# mcat-4cu-b-V2J.net
KiCad netlist of a schematic drawn in EAGLE
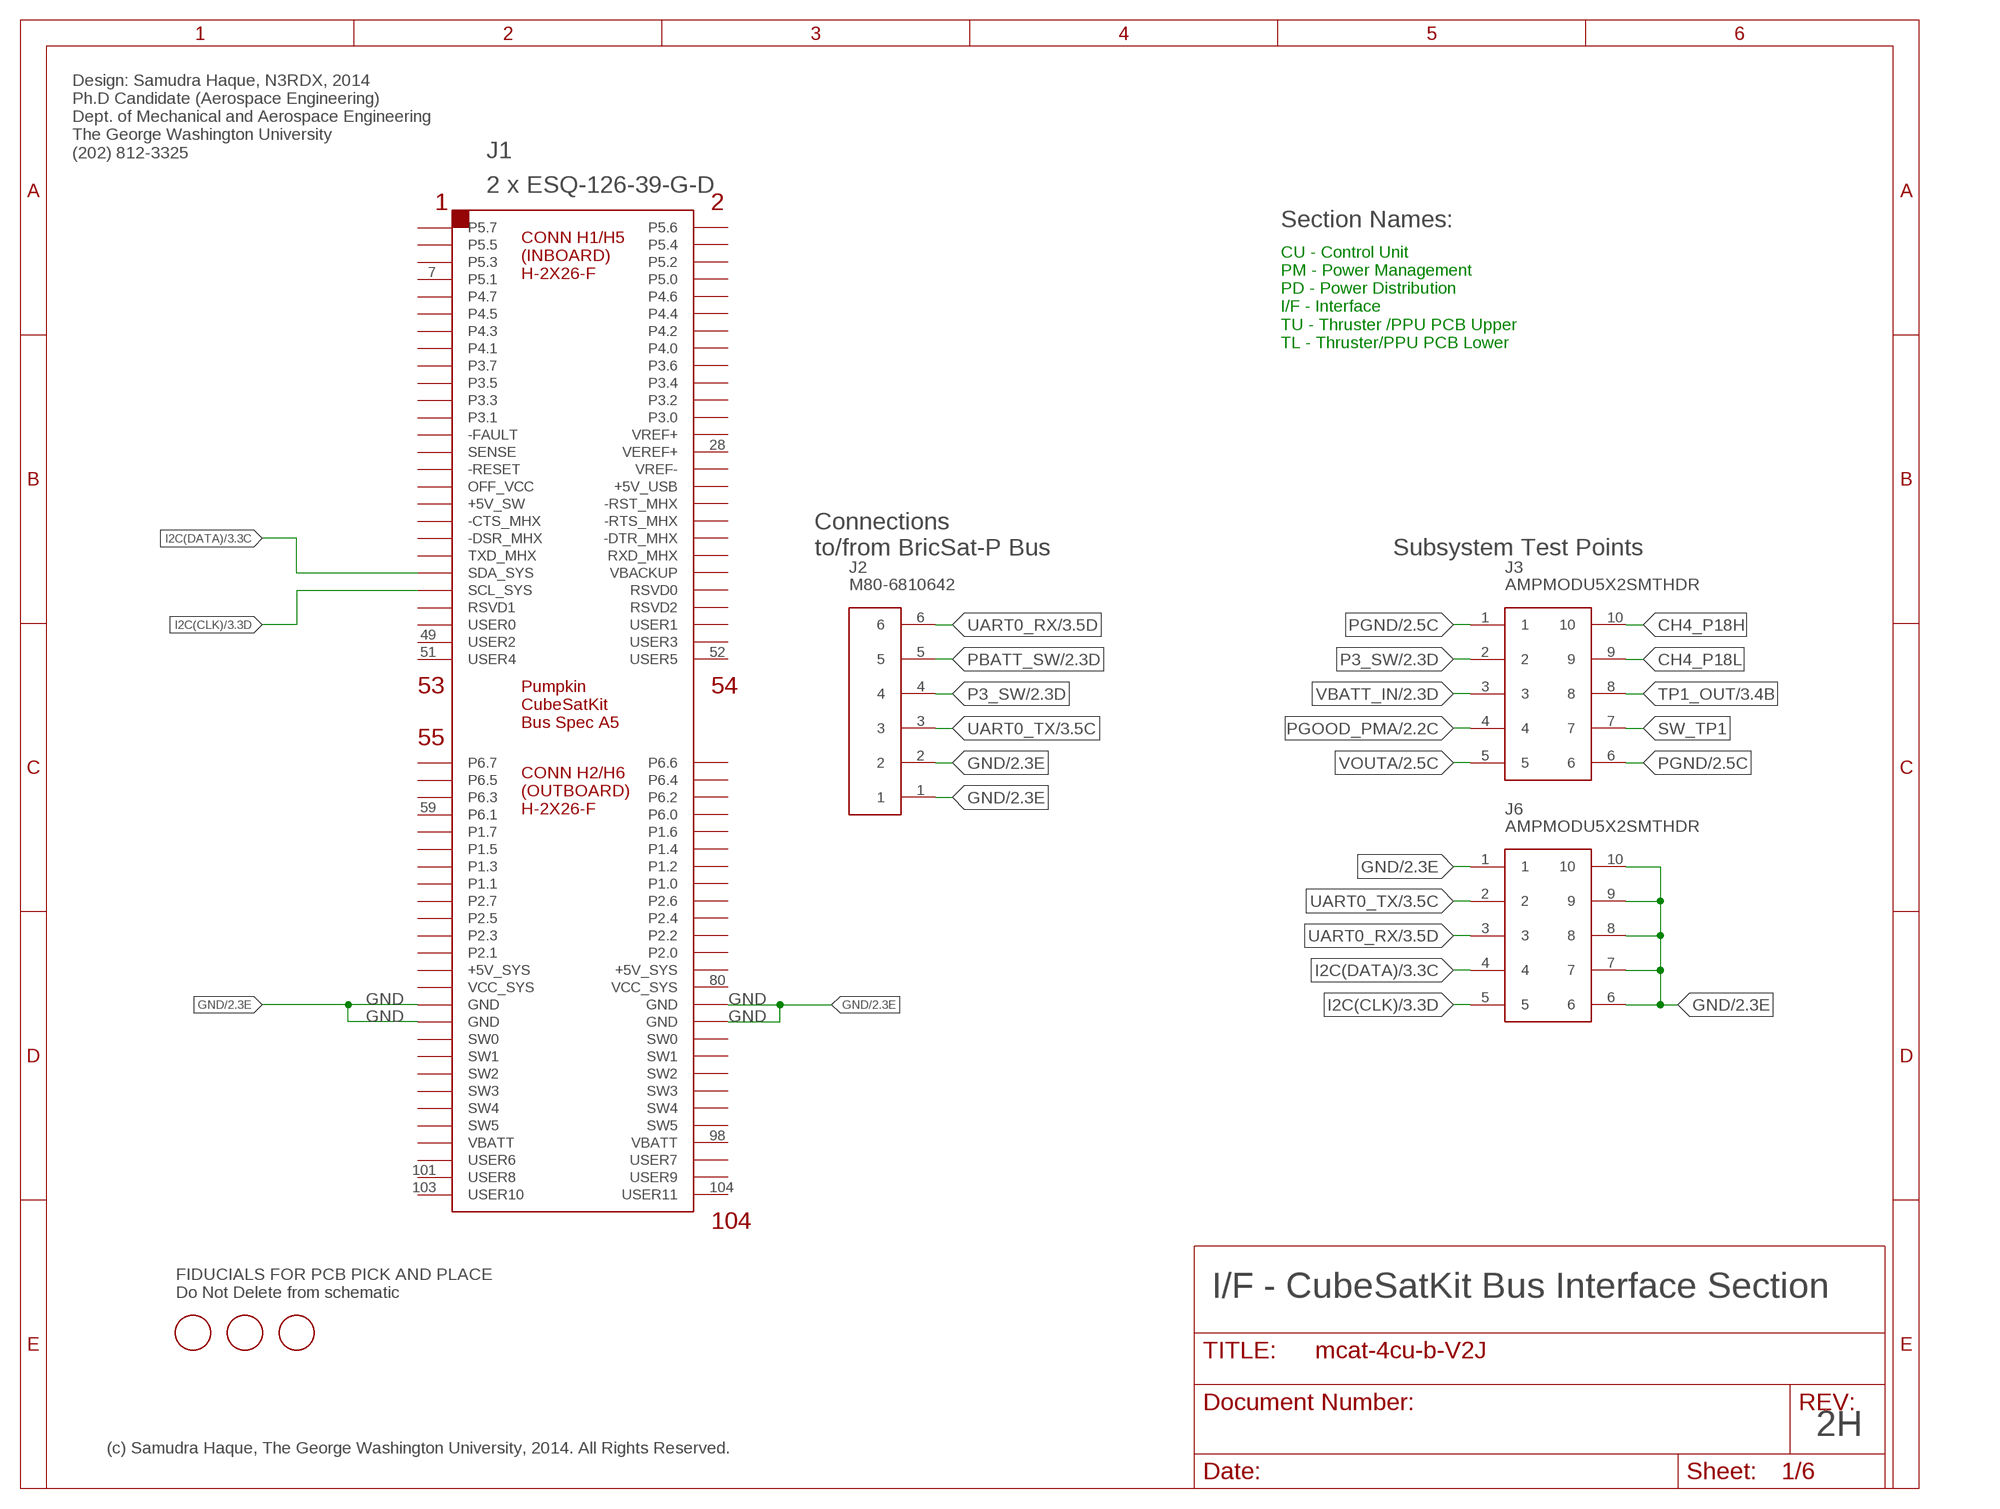
[diagram p0: schematic, sheet 1]
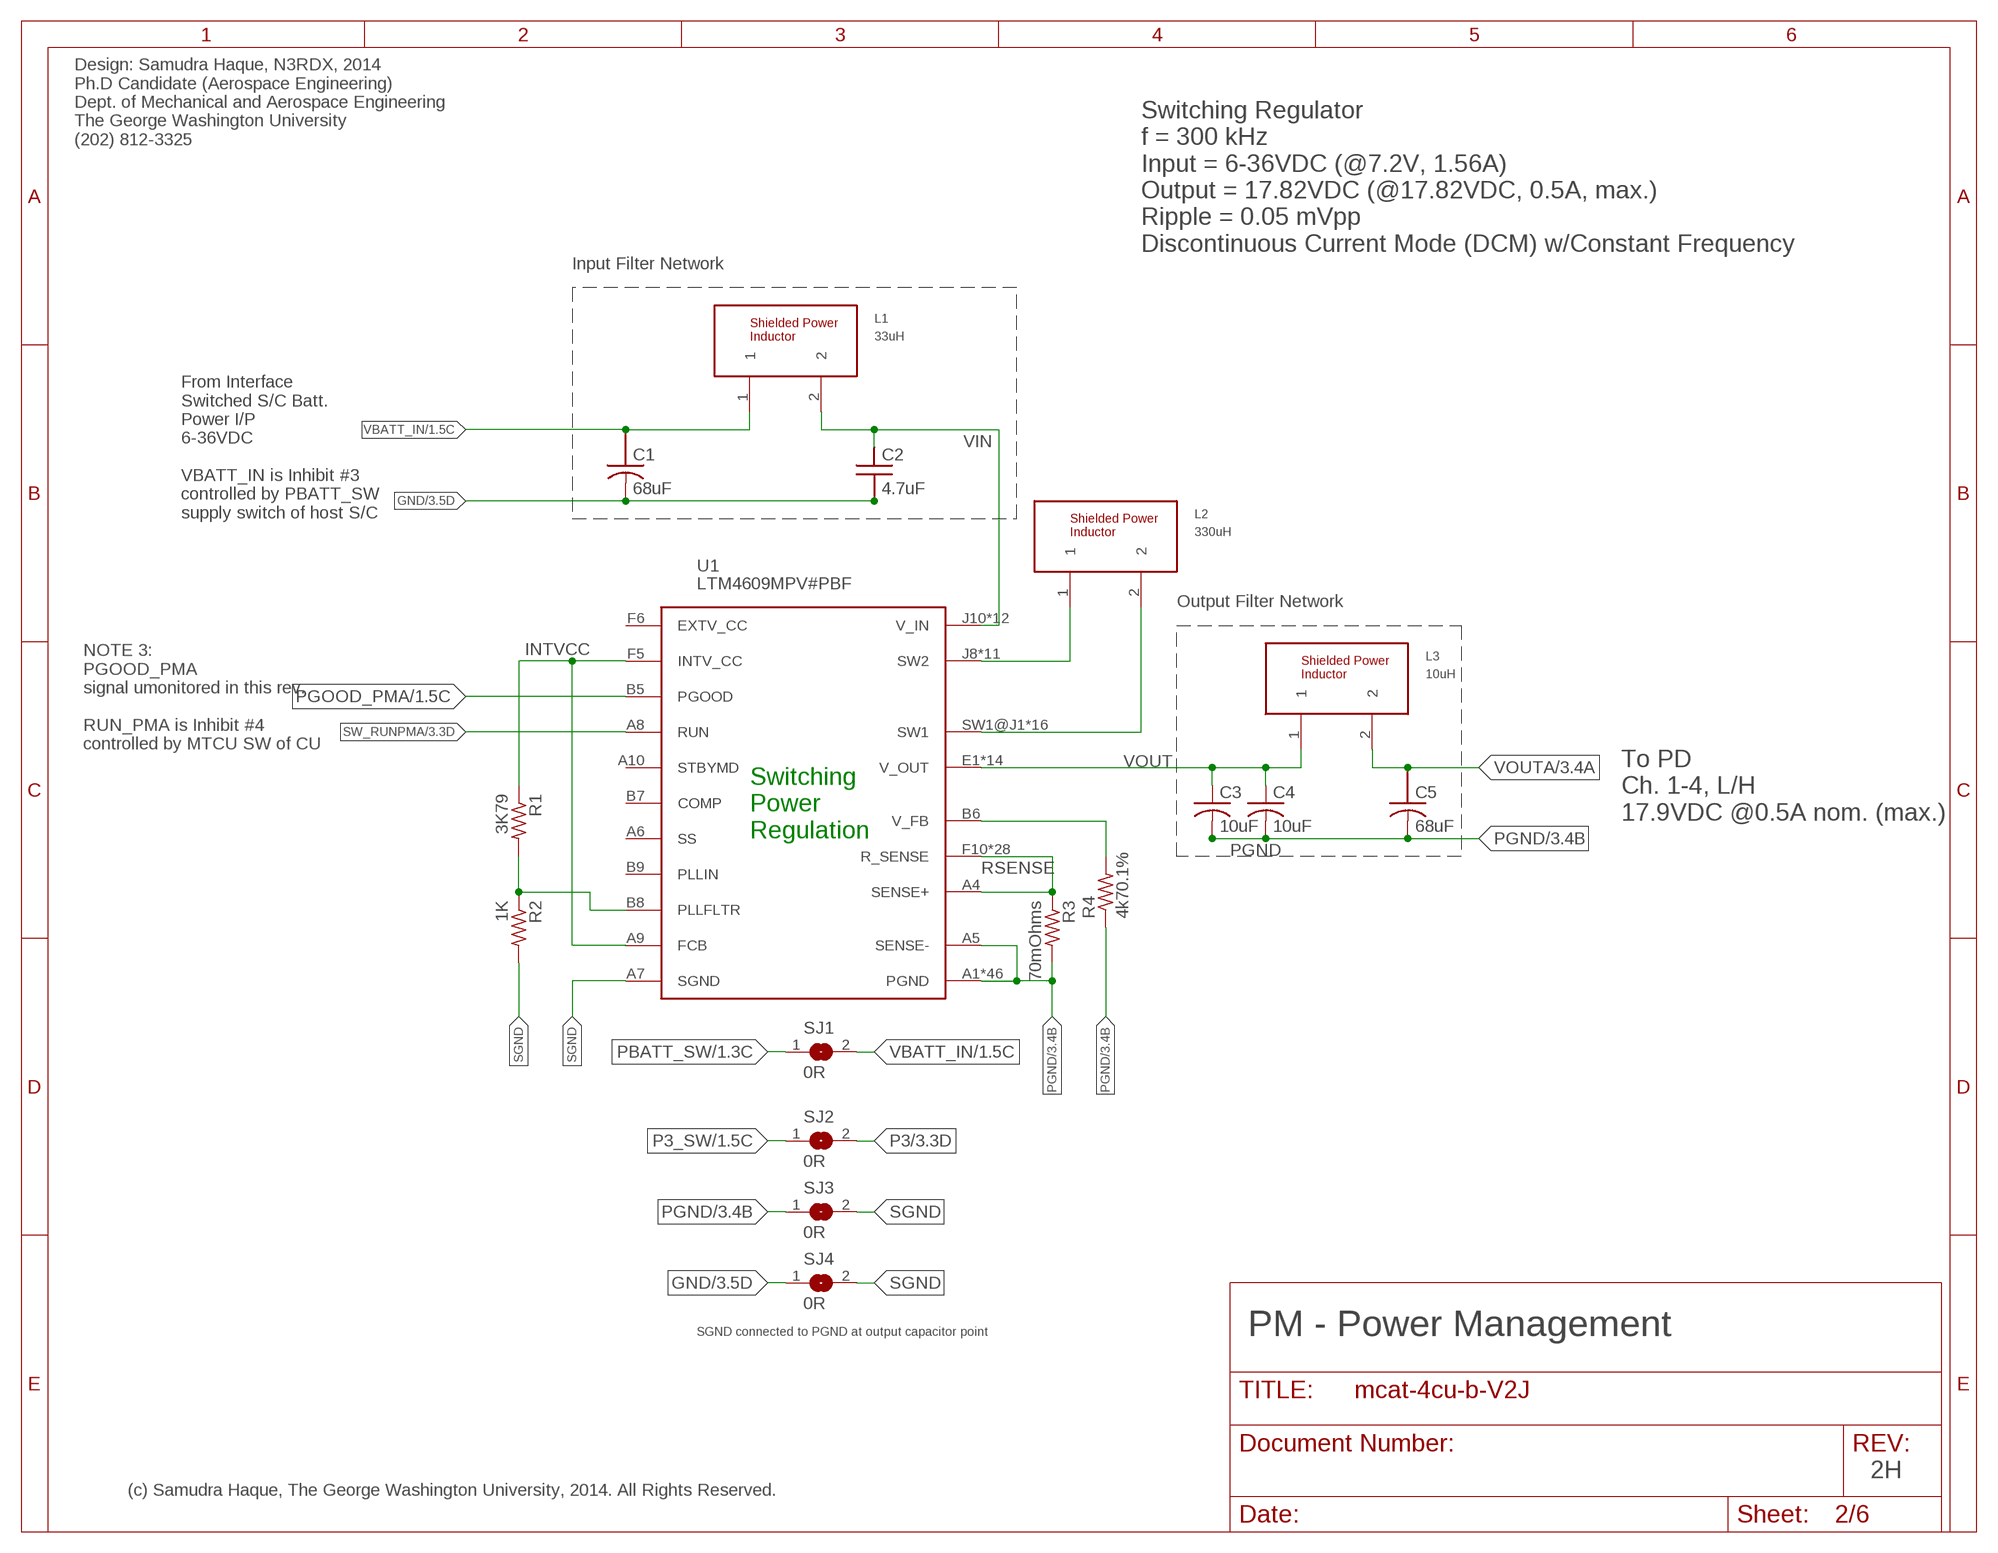
[diagram p1: schematic, sheet 2]
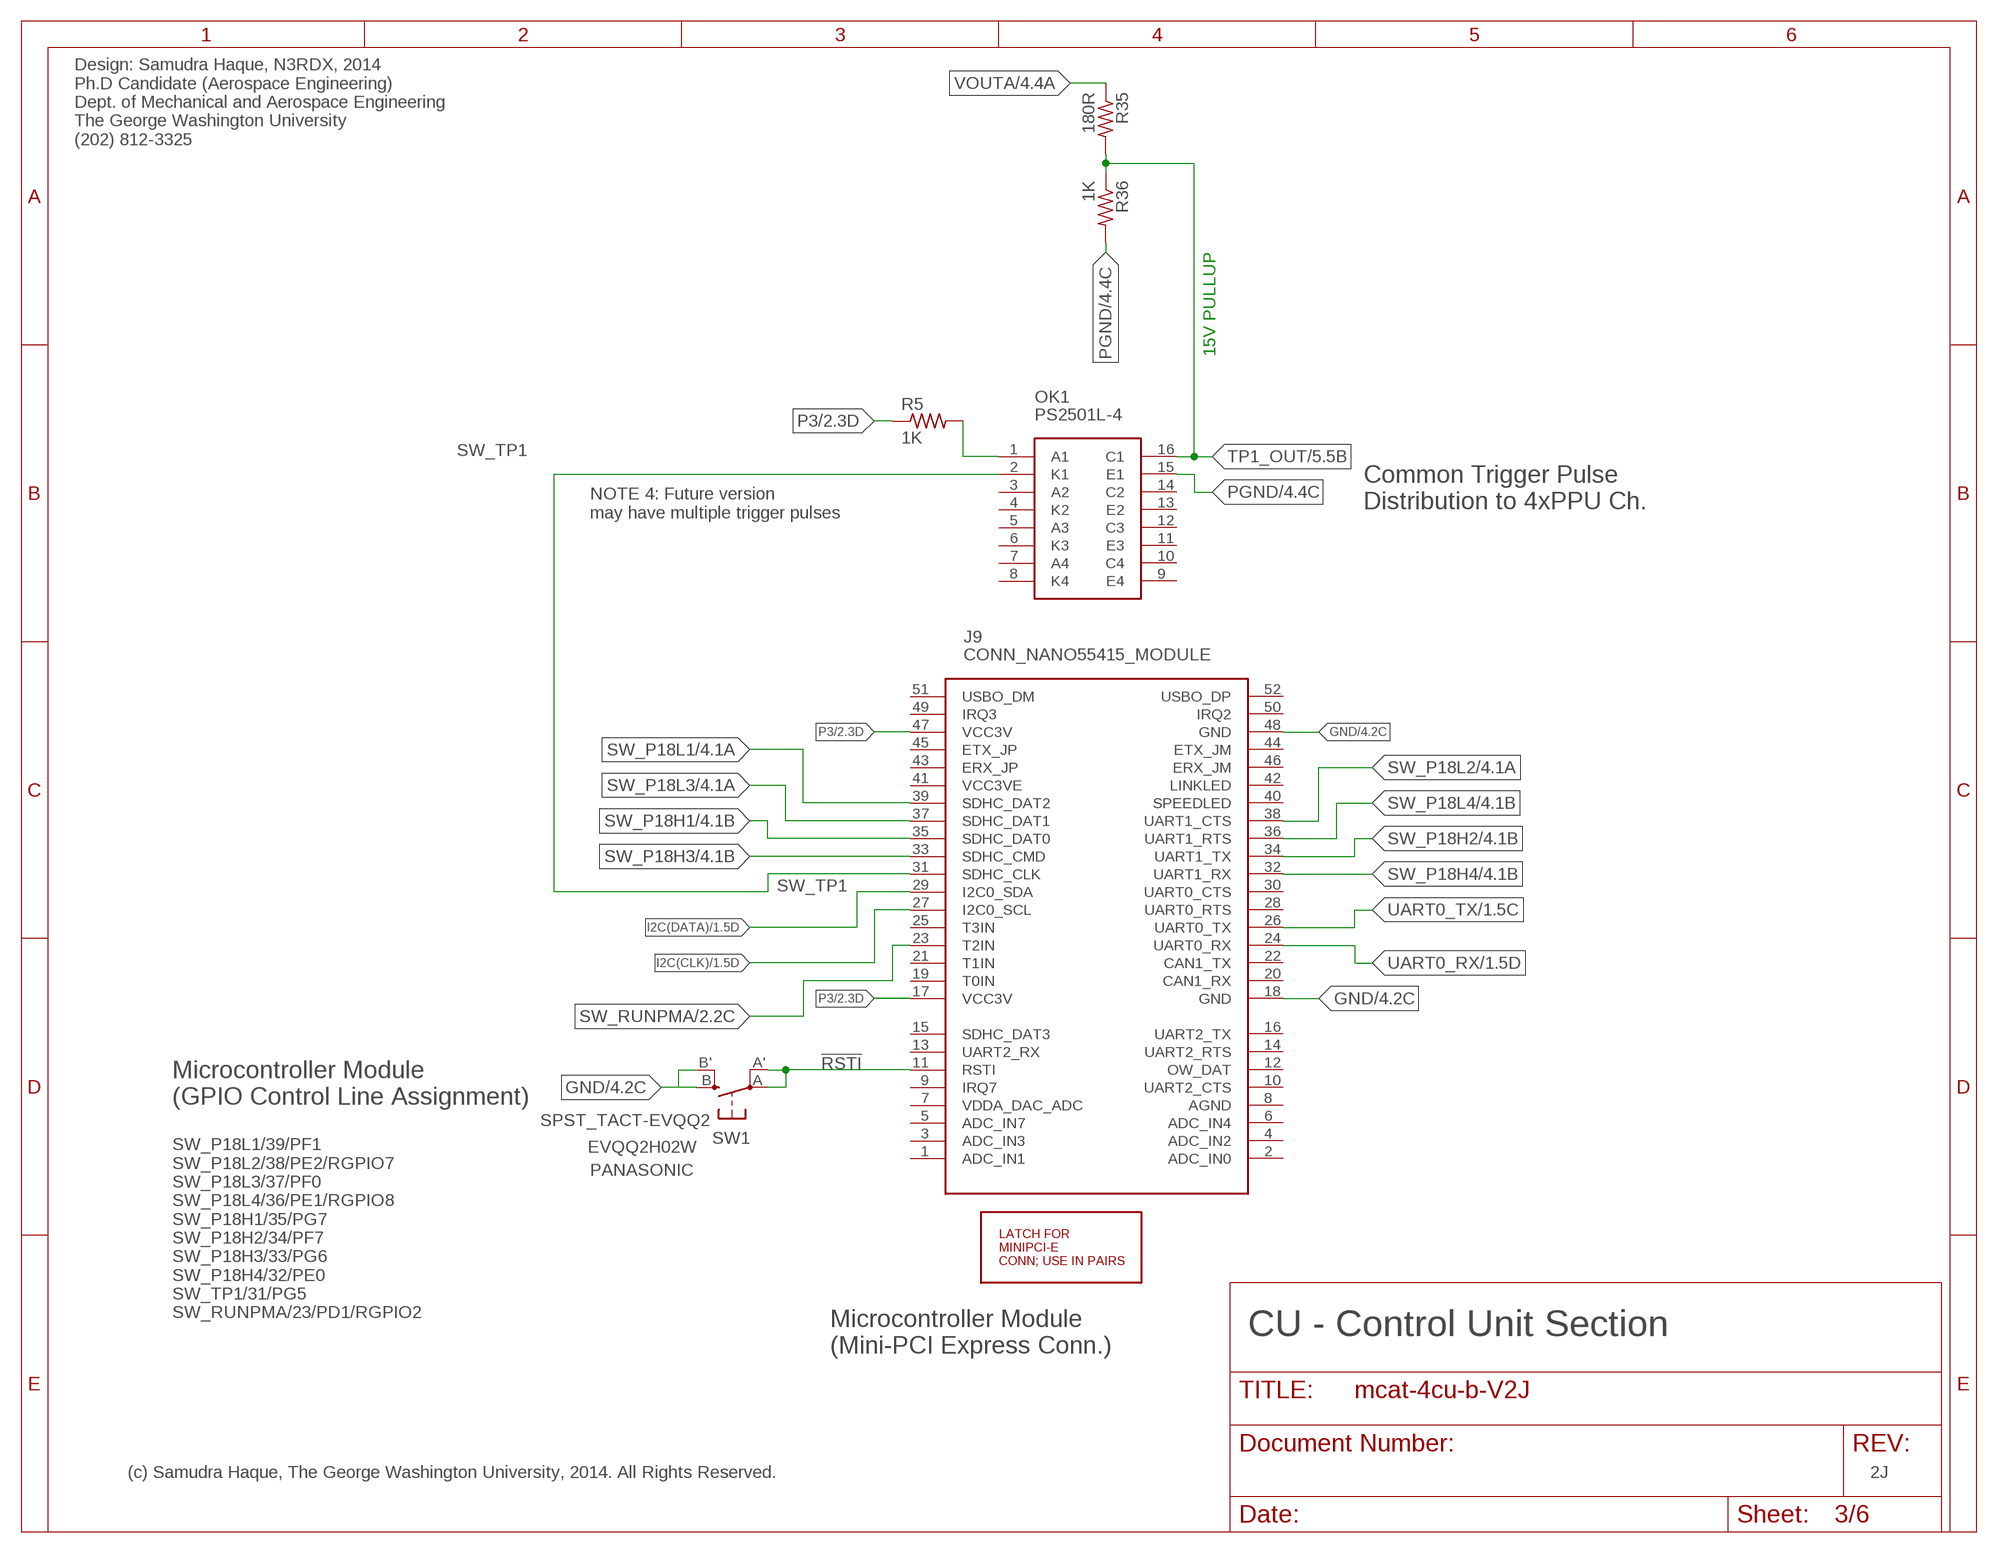
[diagram p2: schematic, sheet 3]
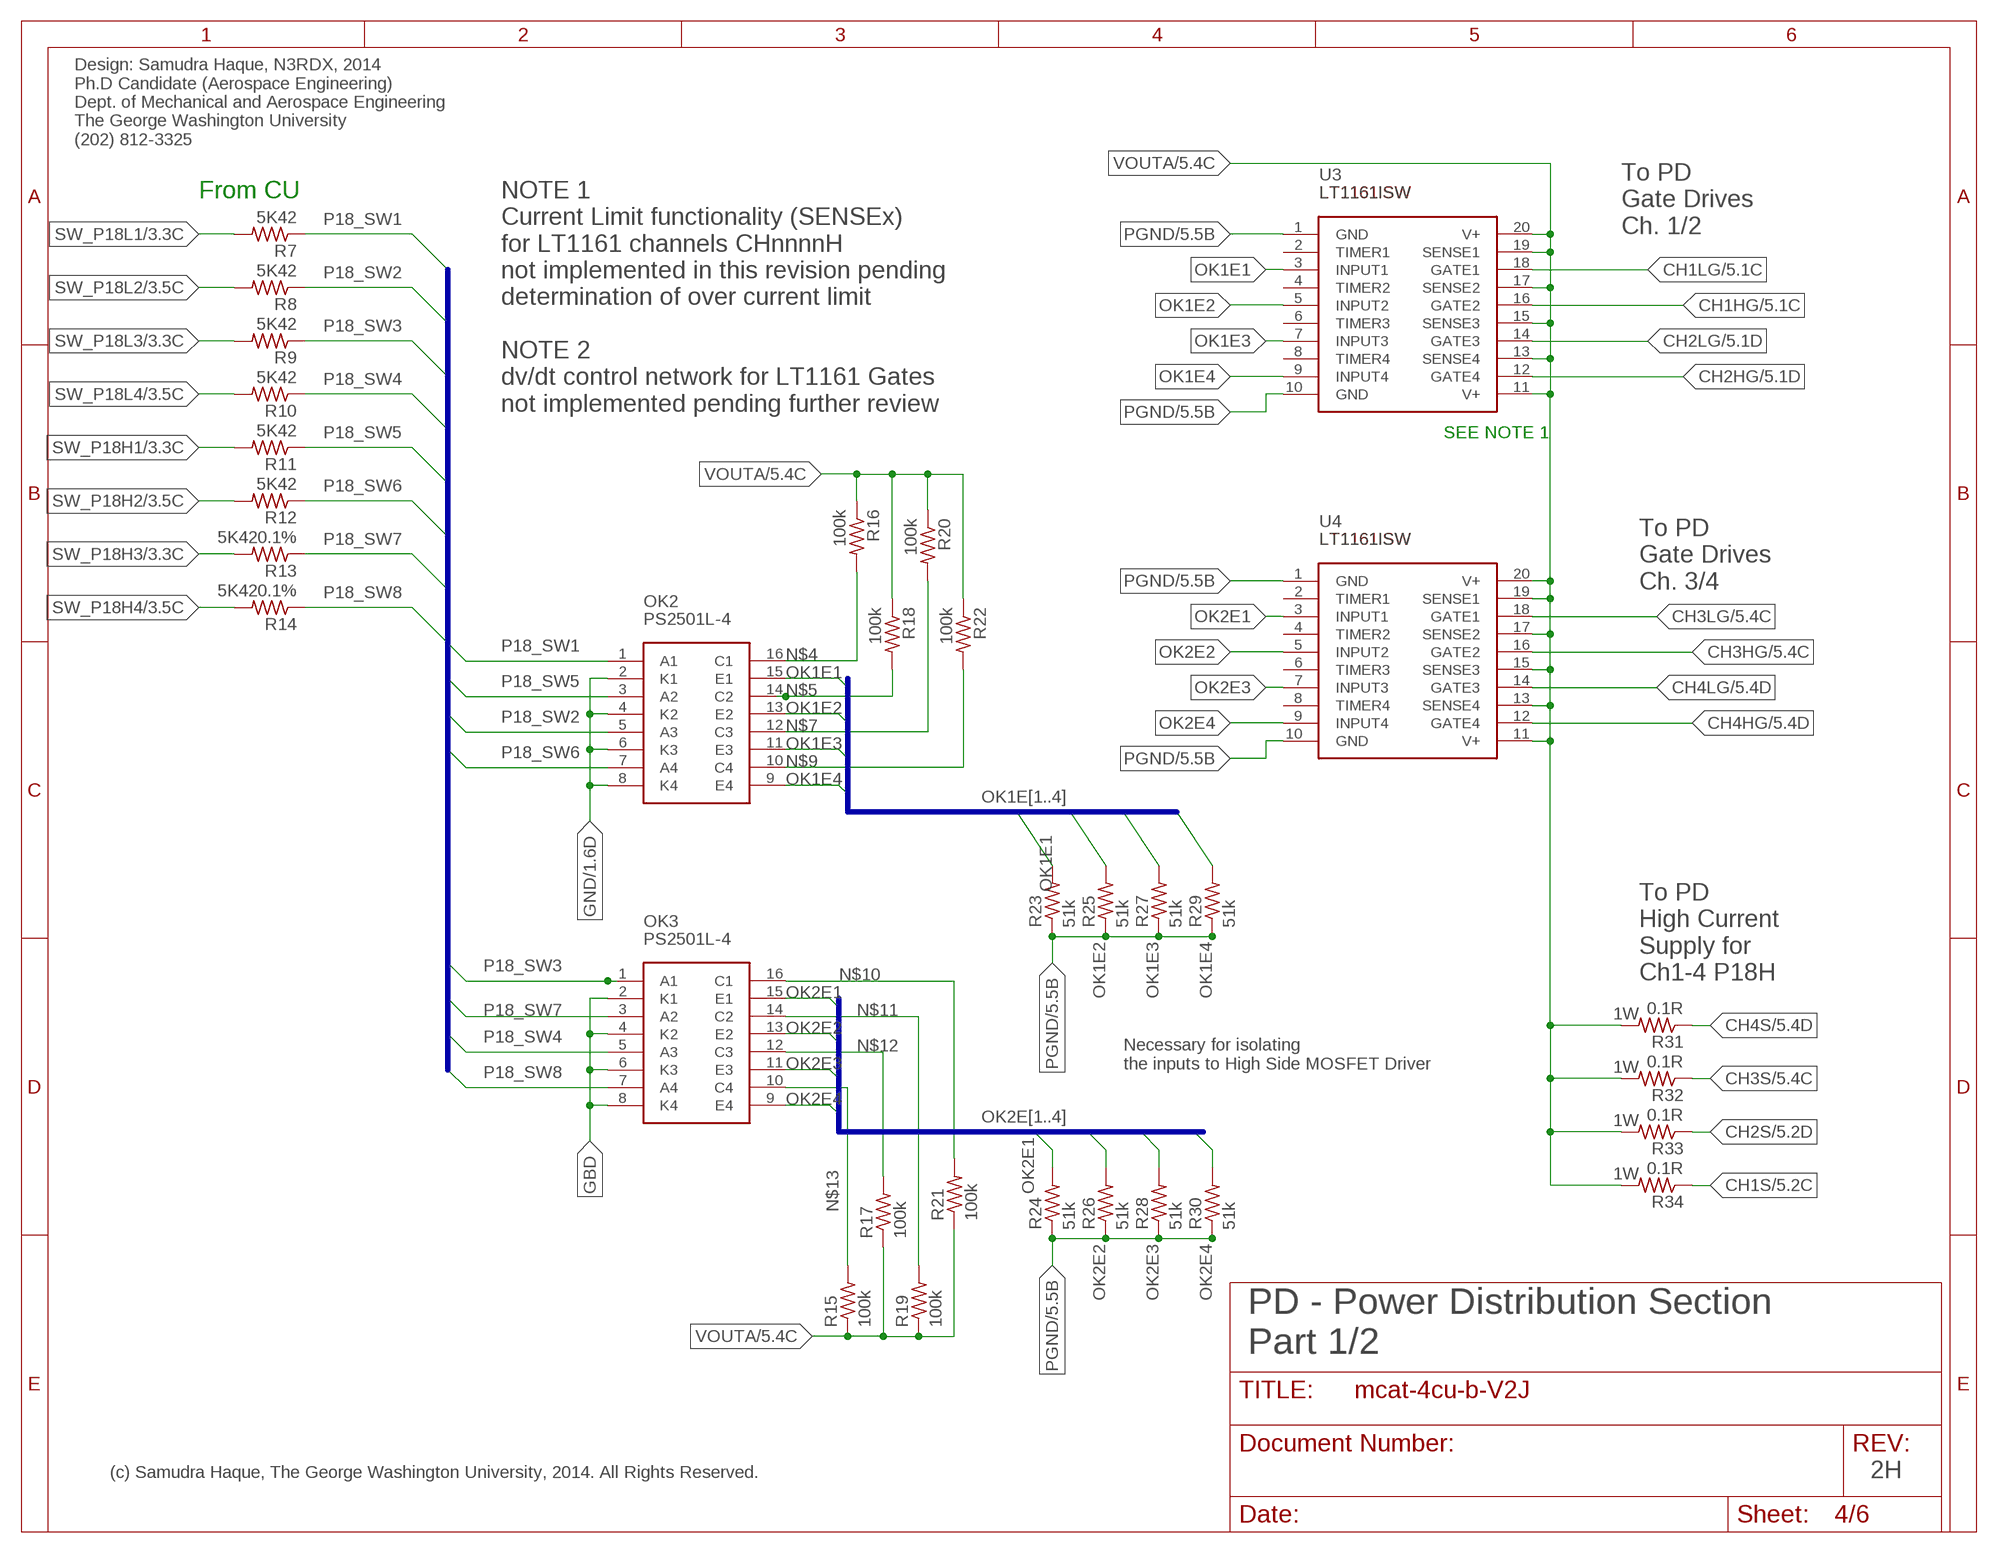
[diagram p3: schematic, sheet 4]
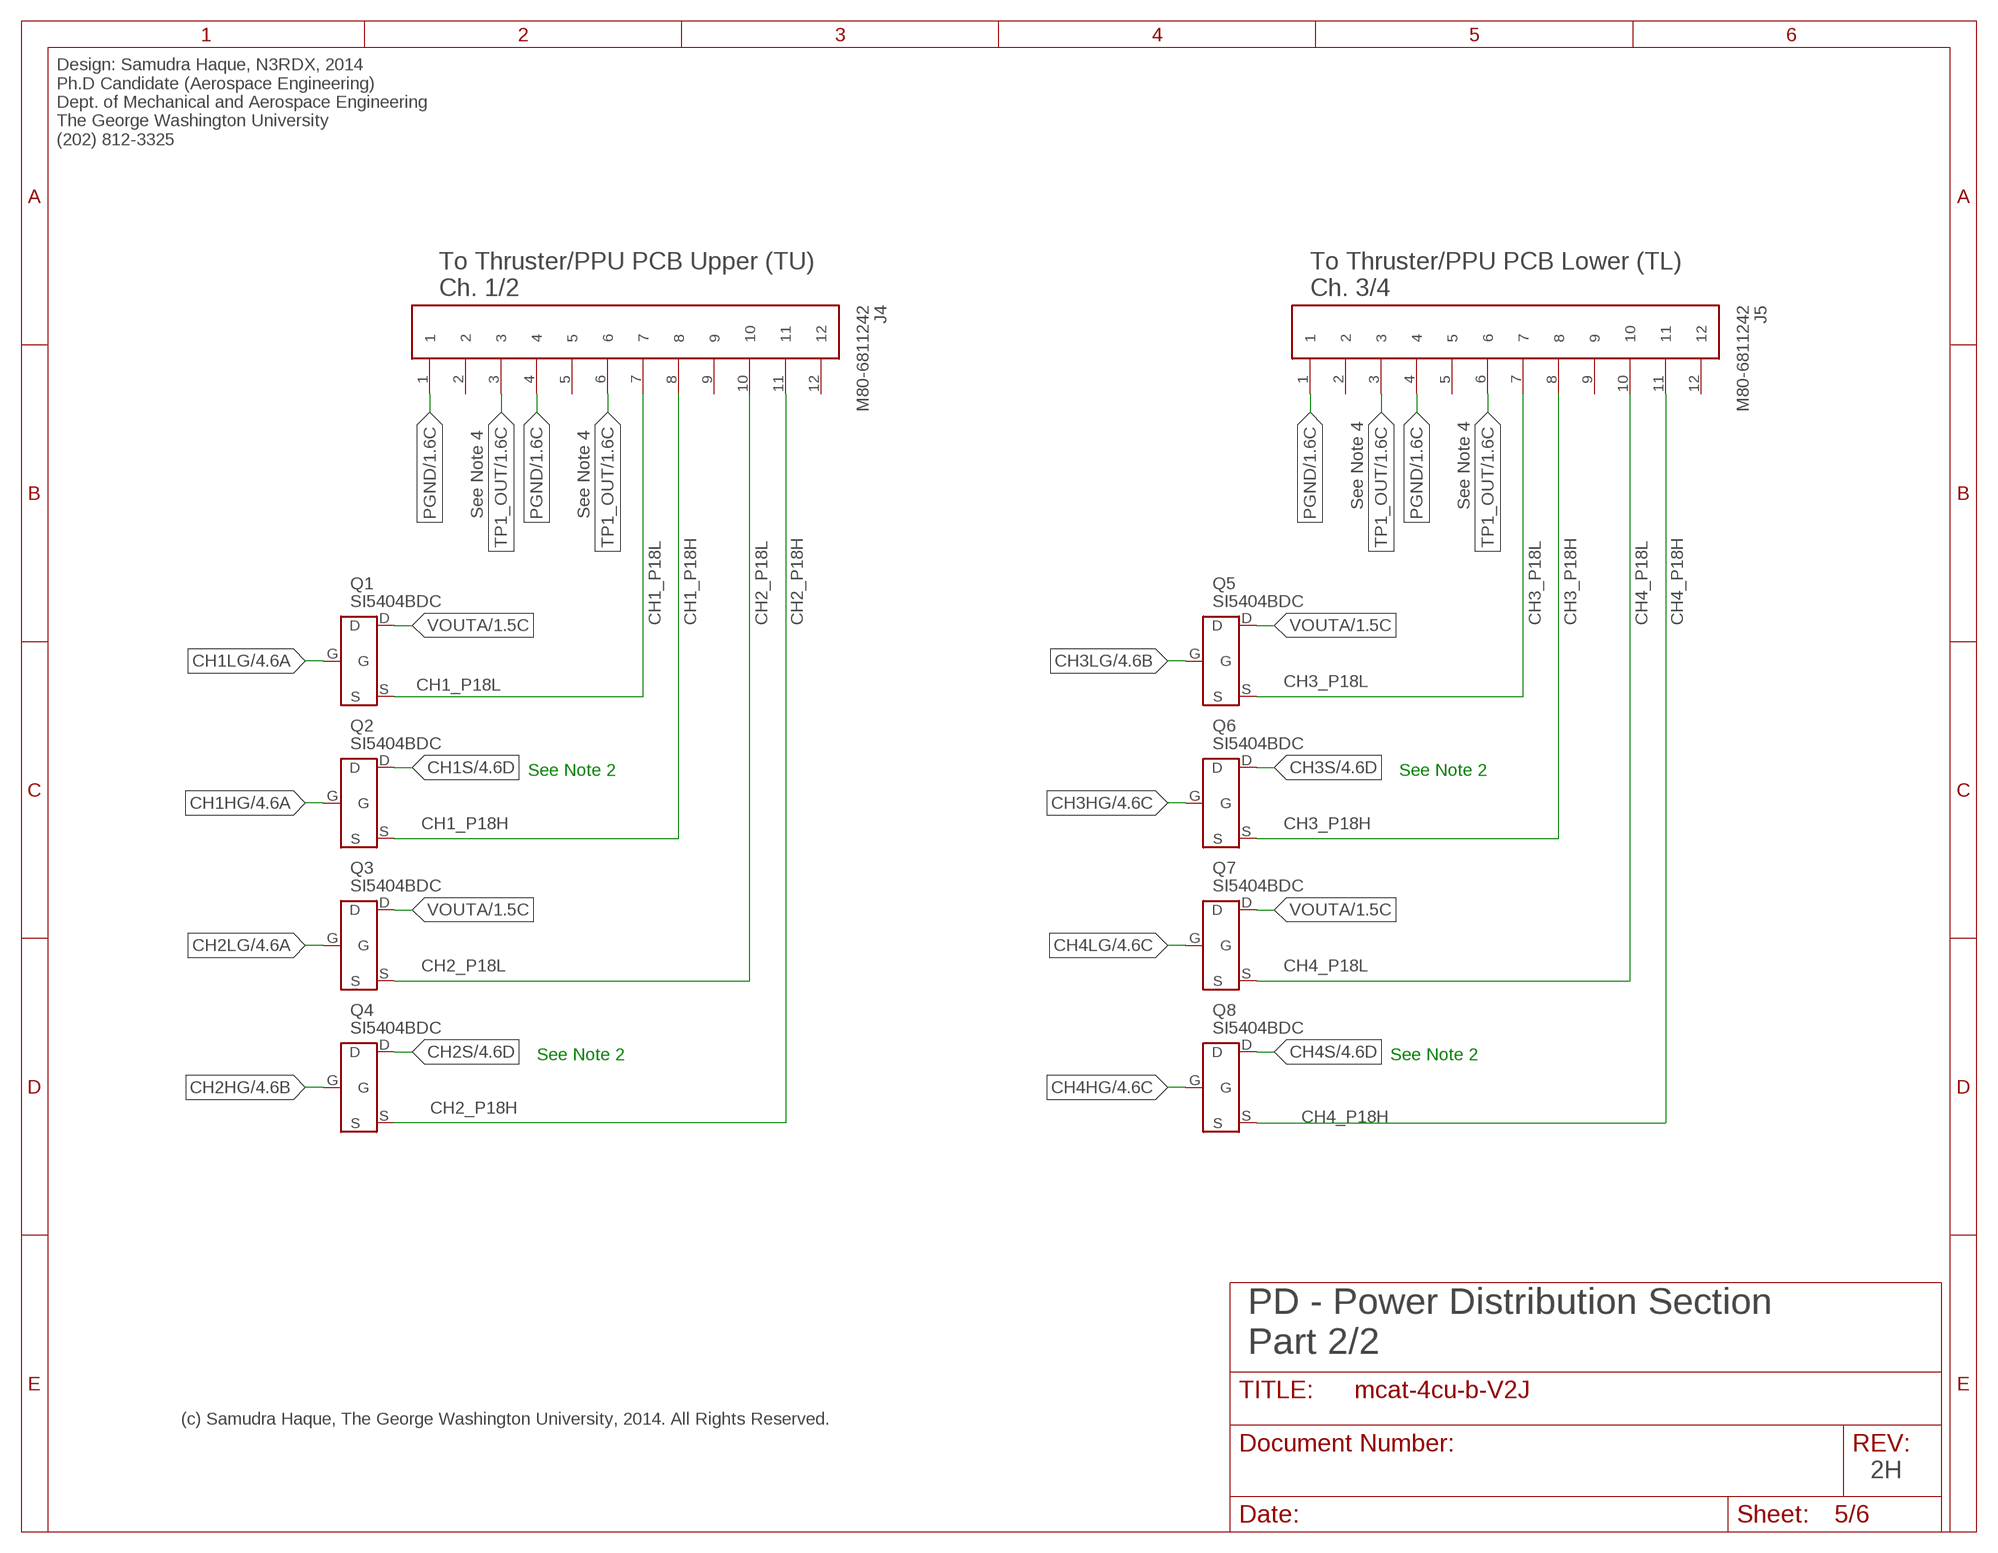
[diagram p4: schematic, sheet 5]

(export (version "E")
  (design (tool "Eeschema 10.0.6"))
  (components
    (comp (ref "J7")
      (value "LATCH_NANO55415_MODULE")
      (footprint "eagle-import:LATCH_SD-48099-400")
      (fields (field (name "MF") "MOLEX") (field (name "MPN") "SD-48099-400"))
      (libsource (lib "eagle-import") (part "LATCH_NANO55415_MODULE"))
    )
    (comp (ref "J9")
      (value "CONN_NANO55415_MODULE")
      (footprint "eagle-import:CONN_SD-67910-001")
      (fields (field (name "MF") "MOLEX") (field (name "MPN") "SD-679101-002"))
      (libsource (lib "eagle-import") (part "CONN_NANO55415_MODULE"))
    )
    (comp (ref "OK1")
      (value "PS2501L-4")
      (footprint "eagle-import:PS2501L-4")
      (fields (field (name "MF") "CEL"))
      (libsource (lib "eagle-import") (part "PS2501L-4"))
    )
    (comp (ref "R5")
      (value "1K")
      (footprint "eagle-import:R0805")
      (fields (field (name "MF") "PANASONIC") (field (name "MPN") "ERA-6AEB102V"))
      (libsource (lib "eagle-import") (part "resistor_R-US_R0805"))
    )
    (comp (ref "R35")
      (value "180R")
      (footprint "eagle-import:R0805")
      (fields (field (name "MF") "PANASONIC") (field (name "MPN") "ERA-6AED181V"))
      (libsource (lib "eagle-import") (part "resistor_R-US_R0805"))
    )
    (comp (ref "R36")
      (value "1K")
      (footprint "eagle-import:R0805")
      (fields (field (name "MF") "PANASONIC") (field (name "MPN") "ERA-6AEB102V"))
      (libsource (lib "eagle-import") (part "resistor_R-US_R0805"))
    )
    (comp (ref "SW1")
      (value "SPST_TACT-EVQQ2")
      (footprint "eagle-import:EVQ-Q2")
      (fields (field (name "MF") "PANASONIC") (field (name "MPN") "EVQQ2H02W"))
      (libsource (lib "eagle-import") (part "SPST_TACT-EVQQ2"))
    )
    (comp (ref "J4")
      (value "M80-6811242")
      (footprint "eagle-import:M80-68112")
      (fields (field (name "MF") "HARWIN"))
      (libsource (lib "eagle-import") (part "M80-6811242"))
    )
    (comp (ref "J5")
      (value "M80-6811242")
      (footprint "eagle-import:M80-68112")
      (fields (field (name "MF") "HARWIN"))
      (libsource (lib "eagle-import") (part "M80-6811242"))
    )
    (comp (ref "Q1")
      (value "SI5404BDC")
      (footprint "eagle-import:1206-8-CHIPFET")
      (fields (field (name "MF") "VISHAY/SILICONIX") (field (name "MPN") "SI5404BDC-T1-E3"))
      (libsource (lib "eagle-import") (part "SI5404BDC"))
    )
    (comp (ref "Q2")
      (value "SI5404BDC")
      (footprint "eagle-import:1206-8-CHIPFET")
      (fields (field (name "MF") "VISHAY/SILICONIX") (field (name "MPN") "SI5404BDC-T1-E3"))
      (libsource (lib "eagle-import") (part "SI5404BDC"))
    )
    (comp (ref "Q3")
      (value "SI5404BDC")
      (footprint "eagle-import:1206-8-CHIPFET")
      (fields (field (name "MF") "VISHAY/SILICONIX") (field (name "MPN") "SI5404BDC-T1-E3"))
      (libsource (lib "eagle-import") (part "SI5404BDC"))
    )
    (comp (ref "Q4")
      (value "SI5404BDC")
      (footprint "eagle-import:1206-8-CHIPFET")
      (fields (field (name "MF") "VISHAY/SILICONIX") (field (name "MPN") "SI5404BDC-T1-E3"))
      (libsource (lib "eagle-import") (part "SI5404BDC"))
    )
    (comp (ref "Q5")
      (value "SI5404BDC")
      (footprint "eagle-import:1206-8-CHIPFET")
      (fields (field (name "MF") "VISHAY/SILICONIX") (field (name "MPN") "SI5404BDC-T1-E3"))
      (libsource (lib "eagle-import") (part "SI5404BDC"))
    )
    (comp (ref "Q6")
      (value "SI5404BDC")
      (footprint "eagle-import:1206-8-CHIPFET")
      (fields (field (name "MF") "VISHAY/SILICONIX") (field (name "MPN") "SI5404BDC-T1-E3"))
      (libsource (lib "eagle-import") (part "SI5404BDC"))
    )
    (comp (ref "Q7")
      (value "SI5404BDC")
      (footprint "eagle-import:1206-8-CHIPFET")
      (fields (field (name "MF") "VISHAY/SILICONIX") (field (name "MPN") "SI5404BDC-T1-E3"))
      (libsource (lib "eagle-import") (part "SI5404BDC"))
    )
    (comp (ref "Q8")
      (value "SI5404BDC")
      (footprint "eagle-import:1206-8-CHIPFET")
      (fields (field (name "MF") "VISHAY/SILICONIX") (field (name "MPN") "SI5404BDC-T1-E3"))
      (libsource (lib "eagle-import") (part "SI5404BDC"))
    )
    (comp (ref "C1")
      (value "68uF")
      (footprint "eagle-import:OS-CON-SVPF-F12")
      (fields (field (name "MF") "OSCON") (field (name "MPN") "50SVPF68M"))
      (libsource (lib "eagle-import") (part "OSCON-50SVPF68M"))
    )
    (comp (ref "C2")
      (value "4.7uF")
      (footprint "eagle-import:MLCC-X7R-1210")
      (fields (field (name "MF") "AVX") (field (name "MPN") "LD105C475KAB2A"))
      (libsource (lib "eagle-import") (part "AVX-LD105C475KAB2A"))
    )
    (comp (ref "C3")
      (value "10uF")
      (footprint "eagle-import:C1210K")
      (fields (field (name "MF") "MURATA") (field (name "MPN") "GRM32ER71H106KA12L"))
      (libsource (lib "eagle-import") (part "C-USC1210K"))
    )
    (comp (ref "C4")
      (value "10uF")
      (footprint "eagle-import:C1210K")
      (fields (field (name "MF") "MURATA") (field (name "MPN") "GRM32ER71H106KA12L"))
      (libsource (lib "eagle-import") (part "C-USC1210K"))
    )
    (comp (ref "C5")
      (value "68uF")
      (footprint "eagle-import:OS-CON-SVPF-F12")
      (fields (field (name "MF") "OSCON") (field (name "MPN") "50SVPF68M"))
      (libsource (lib "eagle-import") (part "OSCON-50SVPF68M"))
    )
    (comp (ref "L1")
      (value "33uH")
      (footprint "eagle-import:MSS1048")
      (fields (field (name "MF") "COILCRAFT") (field (name "MPN") "MSS1038-333ML_"))
      (libsource (lib "eagle-import") (part "MSS1038-333ML_"))
    )
    (comp (ref "L2")
      (value "330uH")
      (footprint "eagle-import:MSS1048")
      (fields (field (name "MF") "COILCRAFT") (field (name "MPN") "MSS1048-334KL_"))
      (libsource (lib "eagle-import") (part "MSS1048-334KL_"))
    )
    (comp (ref "L3")
      (value "10uH")
      (footprint "eagle-import:SERIES-POWER-INDUCTORS")
      (fields (field (name "MF") "PANASONIC") (field (name "MPN") "ELL5PS100M"))
      (libsource (lib "eagle-import") (part "ELL-5PS100M"))
    )
    (comp (ref "R1")
      (value "3K79")
      (footprint "eagle-import:R0805")
      (fields (field (name "MF") "VISHAY") (field (name "MPN") "PAT0805E3791BST1"))
      (libsource (lib "eagle-import") (part "R-US_R0805"))
    )
    (comp (ref "R2")
      (value "1K")
      (footprint "eagle-import:R0805")
      (fields (field (name "MF") "VISHAY") (field (name "MPN") "PAT0805E1001BST1"))
      (libsource (lib "eagle-import") (part "R-US_R0805"))
    )
    (comp (ref "R3")
      (value "70mOhms")
      (footprint "eagle-import:R1206")
      (fields (field (name "MF") "VISHAY") (field (name "MPN") "WSL1206R0700FEB18"))
      (libsource (lib "eagle-import") (part "resistor_R-US_R1206"))
    )
    (comp (ref "R4")
      (value "4k70.1%")
      (footprint "eagle-import:R0603")
      (fields (field (name "MF") "SUSUMU") (field (name "MPN") "RG1608P-472-B-T5"))
      (libsource (lib "eagle-import") (part "resistor_R-US_R0603"))
    )
    (comp (ref "SJ1") (value "0R") (footprint "eagle-import:SJ") (libsource (lib "eagle-import") (part "SJ")))
    (comp (ref "SJ2") (value "0R") (footprint "eagle-import:SJ") (libsource (lib "eagle-import") (part "SJ")))
    (comp (ref "SJ3") (value "0R") (footprint "eagle-import:SJ") (libsource (lib "eagle-import") (part "SJ")))
    (comp (ref "SJ4") (value "0R") (footprint "eagle-import:SJ") (libsource (lib "eagle-import") (part "SJ")))
    (comp (ref "U1")
      (value "LTM4609MPV#PBF")
      (footprint "eagle-import:LGA-141-LTC-05-08-1840-B")
      (fields (field (name "MF") "Linear"))
      (libsource (lib "eagle-import") (part "LTM4609MPV#PBFROHS/HITEMP"))
    )
    (comp (ref "OK2")
      (value "PS2501L-4")
      (footprint "eagle-import:PS2501L-4")
      (fields (field (name "MF") "CEL"))
      (libsource (lib "eagle-import") (part "PS2501L-4"))
    )
    (comp (ref "OK3")
      (value "PS2501L-4")
      (footprint "eagle-import:PS2501L-4")
      (fields (field (name "MF") "CEL"))
      (libsource (lib "eagle-import") (part "PS2501L-4"))
    )
    (comp (ref "R7")
      (value "5K42")
      (footprint "eagle-import:R0805")
      (fields (field (name "MF") "VISHAY") (field (name "MPN") "TNPW08055K42BEEA"))
      (libsource (lib "eagle-import") (part "resistor_R-US_R0805"))
    )
    (comp (ref "R8")
      (value "5K42")
      (footprint "eagle-import:R0805")
      (fields (field (name "MF") "VISHAY") (field (name "MPN") "TNPW08055K42BEEA"))
      (libsource (lib "eagle-import") (part "resistor_R-US_R0805"))
    )
    (comp (ref "R9")
      (value "5K42")
      (footprint "eagle-import:R0805")
      (fields (field (name "MF") "VISHAY") (field (name "MPN") "TNPW08055K42BEEA"))
      (libsource (lib "eagle-import") (part "resistor_R-US_R0805"))
    )
    (comp (ref "R10")
      (value "5K42")
      (footprint "eagle-import:R0805")
      (fields (field (name "MF") "VISHAY") (field (name "MPN") "TNPW08055K42BEEA"))
      (libsource (lib "eagle-import") (part "resistor_R-US_R0805"))
    )
    (comp (ref "R11")
      (value "5K42")
      (footprint "eagle-import:R0805")
      (fields (field (name "MF") "VISHAY") (field (name "MPN") "TNPW08055K42BEEA"))
      (libsource (lib "eagle-import") (part "resistor_R-US_R0805"))
    )
    (comp (ref "R12")
      (value "5K42")
      (footprint "eagle-import:R0805")
      (fields (field (name "MF") "VISHAY") (field (name "MPN") "TNPW08055K42BEEA"))
      (libsource (lib "eagle-import") (part "resistor_R-US_R0805"))
    )
    (comp (ref "R13")
      (value "5K420.1%")
      (footprint "eagle-import:R0805")
      (fields (field (name "MF") "VISHAY") (field (name "MPN") "TNPW08055K42BEEA"))
      (libsource (lib "eagle-import") (part "resistor_R-US_R0805"))
    )
    (comp (ref "R14")
      (value "5K420.1%")
      (footprint "eagle-import:R0805")
      (fields (field (name "MF") "VISHAY") (field (name "MPN") "TNPW08055K42BEEA"))
      (libsource (lib "eagle-import") (part "resistor_R-US_R0805"))
    )
    (comp (ref "R15")
      (value "100k")
      (footprint "eagle-import:R0402")
      (fields (field (name "MF") "YAGEO") (field (name "MPN") "RT0402BRD07100KL"))
      (libsource (lib "eagle-import") (part "resistor_R-US_R0402"))
    )
    (comp (ref "R16")
      (value "100k")
      (footprint "eagle-import:R0402")
      (fields (field (name "MF") "YAGEO") (field (name "MPN") "RT0402BRD07100KL"))
      (libsource (lib "eagle-import") (part "resistor_R-US_R0402"))
    )
    (comp (ref "R17")
      (value "100k")
      (footprint "eagle-import:R0402")
      (fields (field (name "MF") "YAGEO") (field (name "MPN") "RT0402BRD07100KL"))
      (libsource (lib "eagle-import") (part "resistor_R-US_R0402"))
    )
    (comp (ref "R18")
      (value "100k")
      (footprint "eagle-import:R0402")
      (fields (field (name "MF") "YAGEO") (field (name "MPN") "RT0402BRD07100KL"))
      (libsource (lib "eagle-import") (part "resistor_R-US_R0402"))
    )
    (comp (ref "R19")
      (value "100k")
      (footprint "eagle-import:R0402")
      (fields (field (name "MF") "YAGEO") (field (name "MPN") "RT0402BRD07100KL"))
      (libsource (lib "eagle-import") (part "resistor_R-US_R0402"))
    )
    (comp (ref "R20")
      (value "100k")
      (footprint "eagle-import:R0402")
      (fields (field (name "MF") "YAGEO") (field (name "MPN") "RT0402BRD07100KL"))
      (libsource (lib "eagle-import") (part "resistor_R-US_R0402"))
    )
    (comp (ref "R21")
      (value "100k")
      (footprint "eagle-import:R0402")
      (fields (field (name "MF") "YAGEO") (field (name "MPN") "RT0402BRD07100KL"))
      (libsource (lib "eagle-import") (part "resistor_R-US_R0402"))
    )
    (comp (ref "R22")
      (value "100k")
      (footprint "eagle-import:R0402")
      (fields (field (name "MF") "YAGEO") (field (name "MPN") "RT0402BRD07100KL"))
      (libsource (lib "eagle-import") (part "resistor_R-US_R0402"))
    )
    (comp (ref "R23")
      (value "51k")
      (footprint "eagle-import:R0603")
      (fields (field (name "MF") "SUSUMU") (field (name "MPN") "RG1608P-513-B-T5 "))
      (libsource (lib "eagle-import") (part "resistor_R-US_R0603"))
    )
    (comp (ref "R24")
      (value "51k")
      (footprint "eagle-import:R0603")
      (fields (field (name "MF") "SUSUMU") (field (name "MPN") "RG1608P-513-B-T5"))
      (libsource (lib "eagle-import") (part "resistor_R-US_R0603"))
    )
    (comp (ref "R25")
      (value "51k")
      (footprint "eagle-import:R0603")
      (fields (field (name "MF") "SUSUMU") (field (name "MPN") "RG1608P-513-B-T5 "))
      (libsource (lib "eagle-import") (part "resistor_R-US_R0603"))
    )
    (comp (ref "R26")
      (value "51k")
      (footprint "eagle-import:R0603")
      (fields (field (name "MF") "SUSUMU") (field (name "MPN") "RG1608P-513-B-T5"))
      (libsource (lib "eagle-import") (part "resistor_R-US_R0603"))
    )
    (comp (ref "R27")
      (value "51k")
      (footprint "eagle-import:R0603")
      (fields (field (name "MF") "SUSUMU") (field (name "MPN") "RG1608P-513-B-T5"))
      (libsource (lib "eagle-import") (part "resistor_R-US_R0603"))
    )
    (comp (ref "R28")
      (value "51k")
      (footprint "eagle-import:R0603")
      (fields (field (name "MF") "SUSUMU") (field (name "MPN") "RG1608P-513-B-T5"))
      (libsource (lib "eagle-import") (part "resistor_R-US_R0603"))
    )
    (comp (ref "R29")
      (value "51k")
      (footprint "eagle-import:R0603")
      (fields (field (name "MF") "SUSUMU") (field (name "MPN") "RG1608P-513-B-T5"))
      (libsource (lib "eagle-import") (part "resistor_R-US_R0603"))
    )
    (comp (ref "R30")
      (value "51k")
      (footprint "eagle-import:R0603")
      (fields (field (name "MF") "SUSUMU") (field (name "MPN") "RG1608P-513-B-T5"))
      (libsource (lib "eagle-import") (part "resistor_R-US_R0603"))
    )
    (comp (ref "R31")
      (value "0.1R")
      (footprint "eagle-import:R1206")
      (fields
        (field (name "MF") "SUSUMU")
        (field (name "MPN") "PRL1632-R100-F-T1")
        (field (name "RATING") "1W")
      )
      (libsource (lib "eagle-import") (part "R-US_R1206"))
    )
    (comp (ref "R32")
      (value "0.1R")
      (footprint "eagle-import:R1206")
      (fields
        (field (name "MF") "SUSUMU")
        (field (name "MPN") "PRL1632-R100-F-T1")
        (field (name "RATING") "1W")
      )
      (libsource (lib "eagle-import") (part "R-US_R1206"))
    )
    (comp (ref "R33")
      (value "0.1R")
      (footprint "eagle-import:R1206")
      (fields
        (field (name "MF") "SUSUMU")
        (field (name "MPN") "PRL1632-R100-F-T1")
        (field (name "RATING") "1W")
      )
      (libsource (lib "eagle-import") (part "R-US_R1206"))
    )
    (comp (ref "R34")
      (value "0.1R")
      (footprint "eagle-import:R1206")
      (fields
        (field (name "MF") "SUSUMU")
        (field (name "MPN") "PRL1632-R100-F-T1")
        (field (name "RATING") "1W")
      )
      (libsource (lib "eagle-import") (part "R-US_R1206"))
    )
    (comp (ref "U3")
      (value "LT1161ISW")
      (footprint "eagle-import:20-LEAD-PLASTIC-SO")
      (fields (field (name "MF") "LINEAR") (field (name "MPN") "LT1161ISW#TRPBF"))
      (libsource (lib "eagle-import") (part "LT1161ISW"))
    )
    (comp (ref "U4")
      (value "LT1161ISW")
      (footprint "eagle-import:20-LEAD-PLASTIC-SO")
      (fields (field (name "MF") "LINEAR") (field (name "MPN") "LT1161ISW#TRPBF"))
      (libsource (lib "eagle-import") (part "LT1161ISW"))
    )
    (comp (ref "FID1")
      (value "FIDUCIAL")
      (footprint "eagle-import:FIDUCIAL_1MM")
      (libsource (lib "eagle-import") (part "FIDUCIAL"))
    )
    (comp (ref "FID2")
      (value "FIDUCIAL")
      (footprint "eagle-import:FIDUCIAL_1MM")
      (libsource (lib "eagle-import") (part "FIDUCIAL"))
    )
    (comp (ref "FID3")
      (value "FIDUCIAL")
      (footprint "eagle-import:FIDUCIAL_1MM")
      (libsource (lib "eagle-import") (part "FIDUCIAL"))
    )
    (comp (ref "J1")
      (value "2 x ESQ-126-39-G-D")
      (footprint "eagle-import:CSK-BUS-PKG")
      (libsource (lib "eagle-import") (part "CSK-BUS-CONN2X2X26"))
    )
    (comp (ref "J2")
      (value "M80-6810642")
      (footprint "eagle-import:M80-68106")
      (fields (field (name "MF") "HARWIN"))
      (libsource (lib "eagle-import") (part "M80-6810642"))
    )
    (comp (ref "J3")
      (value "AMPMODU5X2SMTHDR")
      (footprint "eagle-import:AMPMODU-SMT-PIN-HEADER-5X2")
      (fields (field (name "MF") "AMPMODU") (field (name "MPN") "146131-4"))
      (libsource (lib "eagle-import") (part "AMPMODU-5-146131-X(5X2)"))
    )
    (comp (ref "J6")
      (value "AMPMODU5X2SMTHDR")
      (footprint "eagle-import:AMPMODU-SMT-PIN-HEADER-5X2")
      (fields (field (name "MF") "AMPMODU") (field (name "MPN") "146131-4"))
      (libsource (lib "eagle-import") (part "AMPMODU-5-146131-X(5X2)"))
    )
  )
  (nets
    (net (code "3") (name "CH1HG") (class "Default")
      (node (ref "Q2") (pin "G") (pinfunction "G_G") (pintype "bidirectional"))
      (node (ref "U3") (pin "16") (pinfunction "GATE2_16") (pintype "bidirectional"))
    )
    (net (code "4") (name "CH1LG") (class "Default")
      (node (ref "Q1") (pin "G") (pinfunction "G_G") (pintype "bidirectional"))
      (node (ref "U3") (pin "18") (pinfunction "GATE1_18") (pintype "bidirectional"))
    )
    (net (code "5") (name "CH1S") (class "Default")
      (node (ref "Q2") (pin "D") (pinfunction "D_D") (pintype "bidirectional"))
      (node (ref "R34") (pin "1") (pinfunction "1_1") (pintype "passive"))
    )
    (net (code "6") (name "CH1_P18H") (class "Default")
      (node (ref "J4") (pin "8") (pinfunction "8_8") (pintype "bidirectional"))
      (node (ref "Q2") (pin "S") (pinfunction "S_S") (pintype "bidirectional"))
    )
    (net (code "7") (name "CH1_P18L") (class "Default")
      (node (ref "J4") (pin "7") (pinfunction "7_7") (pintype "bidirectional"))
      (node (ref "Q1") (pin "S") (pinfunction "S_S") (pintype "bidirectional"))
    )
    (net (code "8") (name "CH2HG") (class "Default")
      (node (ref "Q4") (pin "G") (pinfunction "G_G") (pintype "bidirectional"))
      (node (ref "U3") (pin "12") (pinfunction "GATE4_12") (pintype "bidirectional"))
    )
    (net (code "9") (name "CH2LG") (class "Default")
      (node (ref "Q3") (pin "G") (pinfunction "G_G") (pintype "bidirectional"))
      (node (ref "U3") (pin "14") (pinfunction "GATE3_14") (pintype "bidirectional"))
    )
    (net (code "10") (name "CH2S") (class "Default")
      (node (ref "Q4") (pin "D") (pinfunction "D_D") (pintype "bidirectional"))
      (node (ref "R33") (pin "1") (pinfunction "1_1") (pintype "passive"))
    )
    (net (code "11") (name "CH2_P18H") (class "Default")
      (node (ref "J4") (pin "11") (pinfunction "11_11") (pintype "bidirectional"))
      (node (ref "Q4") (pin "S") (pinfunction "S_S") (pintype "bidirectional"))
    )
    (net (code "12") (name "CH2_P18L") (class "Default")
      (node (ref "J4") (pin "10") (pinfunction "10_10") (pintype "bidirectional"))
      (node (ref "Q3") (pin "S") (pinfunction "S_S") (pintype "bidirectional"))
    )
    (net (code "13") (name "CH3HG") (class "Default")
      (node (ref "Q6") (pin "G") (pinfunction "G_G") (pintype "bidirectional"))
      (node (ref "U4") (pin "16") (pinfunction "GATE2_16") (pintype "bidirectional"))
    )
    (net (code "14") (name "CH3LG") (class "Default")
      (node (ref "Q5") (pin "G") (pinfunction "G_G") (pintype "bidirectional"))
      (node (ref "U4") (pin "18") (pinfunction "GATE1_18") (pintype "bidirectional"))
    )
    (net (code "15") (name "CH3S") (class "Default")
      (node (ref "Q6") (pin "D") (pinfunction "D_D") (pintype "bidirectional"))
      (node (ref "R32") (pin "1") (pinfunction "1_1") (pintype "passive"))
    )
    (net (code "16") (name "CH3_P18H") (class "Default")
      (node (ref "J5") (pin "8") (pinfunction "8_8") (pintype "bidirectional"))
      (node (ref "Q6") (pin "S") (pinfunction "S_S") (pintype "bidirectional"))
    )
    (net (code "17") (name "CH3_P18L") (class "Default")
      (node (ref "J5") (pin "7") (pinfunction "7_7") (pintype "bidirectional"))
      (node (ref "Q5") (pin "S") (pinfunction "S_S") (pintype "bidirectional"))
    )
    (net (code "18") (name "CH4HG") (class "Default")
      (node (ref "Q8") (pin "G") (pinfunction "G_G") (pintype "bidirectional"))
      (node (ref "U4") (pin "12") (pinfunction "GATE4_12") (pintype "bidirectional"))
    )
    (net (code "19") (name "CH4LG") (class "Default")
      (node (ref "Q7") (pin "G") (pinfunction "G_G") (pintype "bidirectional"))
      (node (ref "U4") (pin "14") (pinfunction "GATE3_14") (pintype "bidirectional"))
    )
    (net (code "20") (name "CH4S") (class "Default")
      (node (ref "Q8") (pin "D") (pinfunction "D_D") (pintype "bidirectional"))
      (node (ref "R31") (pin "1") (pinfunction "1_1") (pintype "passive"))
    )
    (net (code "21") (name "CH4_P18H") (class "Default")
      (node (ref "J3") (pin "10") (pinfunction "10_10") (pintype "bidirectional"))
      (node (ref "J5") (pin "11") (pinfunction "11_11") (pintype "bidirectional"))
      (node (ref "Q8") (pin "S") (pinfunction "S_S") (pintype "bidirectional"))
    )
    (net (code "22") (name "CH4_P18L") (class "Default")
      (node (ref "J3") (pin "9") (pinfunction "9_9") (pintype "bidirectional"))
      (node (ref "J5") (pin "10") (pinfunction "10_10") (pintype "bidirectional"))
      (node (ref "Q7") (pin "S") (pinfunction "S_S") (pintype "bidirectional"))
    )
    (net (code "23") (name "GBD") (class "Default")
      (node (ref "OK3") (pin "2") (pinfunction "K1_2") (pintype "bidirectional"))
      (node (ref "OK3") (pin "4") (pinfunction "K2_4") (pintype "bidirectional"))
      (node (ref "OK3") (pin "6") (pinfunction "K3_6") (pintype "bidirectional"))
      (node (ref "OK3") (pin "8") (pinfunction "K4_8") (pintype "bidirectional"))
    )
    (net (code "24") (name "GND") (class "Default")
      (node (ref "C1") (pin "K1") (pinfunction "K_K1") (pintype "passive"))
      (node (ref "C2") (pin "2") (pinfunction "2_2") (pintype "passive"))
      (node (ref "J1") (pin "81") (pinfunction "GND_81") (pintype "bidirectional"))
      (node (ref "J1") (pin "82") (pinfunction "GND_82") (pintype "bidirectional"))
      (node (ref "J1") (pin "83") (pinfunction "GND_83") (pintype "bidirectional"))
      (node (ref "J1") (pin "84") (pinfunction "GND_84") (pintype "bidirectional"))
      (node (ref "J2") (pin "1") (pinfunction "1_1") (pintype "bidirectional"))
      (node (ref "J2") (pin "2") (pinfunction "2_2") (pintype "bidirectional"))
      (node (ref "J6") (pin "1") (pinfunction "1_1") (pintype "bidirectional"))
      (node (ref "J6") (pin "10") (pinfunction "10_10") (pintype "bidirectional"))
      (node (ref "J6") (pin "6") (pinfunction "6_6") (pintype "bidirectional"))
      (node (ref "J6") (pin "7") (pinfunction "7_7") (pintype "bidirectional"))
      (node (ref "J6") (pin "8") (pinfunction "8_8") (pintype "bidirectional"))
      (node (ref "J6") (pin "9") (pinfunction "9_9") (pintype "bidirectional"))
      (node (ref "J9") (pin "18") (pinfunction "GND_18") (pintype "bidirectional"))
      (node (ref "J9") (pin "48") (pinfunction "GND_48") (pintype "bidirectional"))
      (node (ref "OK2") (pin "2") (pinfunction "K1_2") (pintype "bidirectional"))
      (node (ref "OK2") (pin "4") (pinfunction "K2_4") (pintype "bidirectional"))
      (node (ref "OK2") (pin "6") (pinfunction "K3_6") (pintype "bidirectional"))
      (node (ref "OK2") (pin "8") (pinfunction "K4_8") (pintype "bidirectional"))
      (node (ref "SJ4") (pin "1") (pinfunction "1_1") (pintype "passive"))
      (node (ref "SW1") (pin "B") (pinfunction "S_B") (pintype "passive"))
      (node (ref "SW1") (pin "B'") (pinfunction "S1_B'") (pintype "passive"))
    )
    (net (code "25") (name "I2C(CLK)") (class "Default")
      (node (ref "J1") (pin "43") (pinfunction "SCL_SYS_43") (pintype "bidirectional"))
      (node (ref "J6") (pin "5") (pinfunction "5_5") (pintype "bidirectional"))
      (node (ref "J9") (pin "27") (pinfunction "I2C0_SCL_27") (pintype "bidirectional"))
    )
    (net (code "26") (name "I2C(DATA)") (class "Default")
      (node (ref "J1") (pin "41") (pinfunction "SDA_SYS_41") (pintype "bidirectional"))
      (node (ref "J6") (pin "4") (pinfunction "4_4") (pintype "bidirectional"))
      (node (ref "J9") (pin "29") (pinfunction "I2C0_SDA_29") (pintype "bidirectional"))
    )
    (net (code "27") (name "INTVCC") (class "Default")
      (node (ref "R1") (pin "1") (pinfunction "1_1") (pintype "passive"))
      (node (ref "U1") (pin "A9") (pinfunction "FCB_A9") (pintype "bidirectional"))
      (node (ref "U1") (pin "F5") (pinfunction "INTV_CC_F5") (pintype "bidirectional"))
    )
    (net (code "28") (name "N$4") (class "Default")
      (node (ref "OK2") (pin "16") (pinfunction "C1_16") (pintype "bidirectional"))
      (node (ref "R16") (pin "2") (pinfunction "2_2") (pintype "passive"))
    )
    (net (code "29") (name "N$5") (class "Default")
      (node (ref "OK2") (pin "14") (pinfunction "C2_14") (pintype "bidirectional"))
      (node (ref "R18") (pin "2") (pinfunction "2_2") (pintype "passive"))
    )
    (net (code "30") (name "N$7") (class "Default")
      (node (ref "OK2") (pin "12") (pinfunction "C3_12") (pintype "bidirectional"))
      (node (ref "R20") (pin "2") (pinfunction "2_2") (pintype "passive"))
    )
    (net (code "31") (name "N$9") (class "Default")
      (node (ref "OK2") (pin "10") (pinfunction "C4_10") (pintype "bidirectional"))
      (node (ref "R22") (pin "2") (pinfunction "2_2") (pintype "passive"))
    )
    (net (code "32") (name "N$10") (class "Default")
      (node (ref "OK3") (pin "16") (pinfunction "C1_16") (pintype "bidirectional"))
      (node (ref "R21") (pin "2") (pinfunction "2_2") (pintype "passive"))
    )
    (net (code "33") (name "N$11") (class "Default")
      (node (ref "OK3") (pin "14") (pinfunction "C2_14") (pintype "bidirectional"))
      (node (ref "R19") (pin "2") (pinfunction "2_2") (pintype "passive"))
    )
    (net (code "34") (name "N$12") (class "Default")
      (node (ref "OK3") (pin "12") (pinfunction "C3_12") (pintype "bidirectional"))
      (node (ref "R17") (pin "2") (pinfunction "2_2") (pintype "passive"))
    )
    (net (code "35") (name "N$13") (class "Default")
      (node (ref "OK3") (pin "10") (pinfunction "C4_10") (pintype "bidirectional"))
      (node (ref "R15") (pin "2") (pinfunction "2_2") (pintype "passive"))
    )
    (net (code "36") (name "Net-(L2-Pad1)") (class "Default")
      (node (ref "L2") (pin "1") (pinfunction "1_1") (pintype "bidirectional"))
      (node (ref "U1") (pin "J8") (pinfunction "SW2_J8") (pintype "bidirectional"))
      (node (ref "U1") (pin "J9") (pinfunction "SW2_J9") (pintype "bidirectional"))
      (node (ref "U1") (pin "K7") (pinfunction "SW2_K7") (pintype "bidirectional"))
      (node (ref "U1") (pin "K8") (pinfunction "SW2_K8") (pintype "bidirectional"))
      (node (ref "U1") (pin "K9") (pinfunction "SW2_K9") (pintype "bidirectional"))
      (node (ref "U1") (pin "L7") (pinfunction "SW2_L7") (pintype "bidirectional"))
      (node (ref "U1") (pin "L8") (pinfunction "SW2_L8") (pintype "bidirectional"))
      (node (ref "U1") (pin "L9") (pinfunction "SW2_L9") (pintype "bidirectional"))
      (node (ref "U1") (pin "M7") (pinfunction "SW2_M7") (pintype "bidirectional"))
      (node (ref "U1") (pin "M8") (pinfunction "SW2_M8") (pintype "bidirectional"))
      (node (ref "U1") (pin "M9") (pinfunction "SW2_M9") (pintype "bidirectional"))
    )
    (net (code "37") (name "Net-(L2-Pad2)") (class "Default")
      (node (ref "L2") (pin "2") (pinfunction "2_2") (pintype "bidirectional"))
      (node (ref "U1") (pin "SW1@J1") (pinfunction "SW1_SW1@J1") (pintype "bidirectional"))
      (node (ref "U1") (pin "SW1@J2") (pinfunction "SW1_SW1@J2") (pintype "bidirectional"))
      (node (ref "U1") (pin "SW1@J3") (pinfunction "SW1_SW1@J3") (pintype "bidirectional"))
      (node (ref "U1") (pin "SW1@J4") (pinfunction "SW1_SW1@J4") (pintype "bidirectional"))
      (node (ref "U1") (pin "SW1@K1") (pinfunction "SW1_SW1@K1") (pintype "bidirectional"))
      (node (ref "U1") (pin "SW1@K2") (pinfunction "SW1_SW1@K2") (pintype "bidirectional"))
      (node (ref "U1") (pin "SW1@K3") (pinfunction "SW1_SW1@K3") (pintype "bidirectional"))
      (node (ref "U1") (pin "SW1@K4") (pinfunction "SW1_SW1@K4") (pintype "bidirectional"))
      (node (ref "U1") (pin "SW1@L1") (pinfunction "SW1_SW1@L1") (pintype "bidirectional"))
      (node (ref "U1") (pin "SW1@L2") (pinfunction "SW1_SW1@L2") (pintype "bidirectional"))
      (node (ref "U1") (pin "SW1@L3") (pinfunction "SW1_SW1@L3") (pintype "bidirectional"))
      (node (ref "U1") (pin "SW1@L4") (pinfunction "SW1_SW1@L4") (pintype "bidirectional"))
      (node (ref "U1") (pin "SW1@M1") (pinfunction "SW1_SW1@M1") (pintype "bidirectional"))
      (node (ref "U1") (pin "SW1@M2") (pinfunction "SW1_SW1@M2") (pintype "bidirectional"))
      (node (ref "U1") (pin "SW1@M3") (pinfunction "SW1_SW1@M3") (pintype "bidirectional"))
      (node (ref "U1") (pin "SW1@M4") (pinfunction "SW1_SW1@M4") (pintype "bidirectional"))
    )
    (net (code "38") (name "Net-(OK1-A1)") (class "Default")
      (node (ref "OK1") (pin "1") (pinfunction "A1_1") (pintype "bidirectional"))
      (node (ref "R5") (pin "2") (pinfunction "2_2") (pintype "passive"))
    )
    (net (code "39") (name "Net-(U1-PLLFLTR)") (class "Default")
      (node (ref "R1") (pin "2") (pinfunction "2_2") (pintype "passive"))
      (node (ref "R2") (pin "1") (pinfunction "1_1") (pintype "passive"))
      (node (ref "U1") (pin "B8") (pinfunction "PLLFLTR_B8") (pintype "bidirectional"))
    )
    (net (code "40") (name "Net-(U1-V_FB)") (class "Default")
      (node (ref "R4") (pin "2") (pinfunction "2_2") (pintype "passive"))
      (node (ref "U1") (pin "B6") (pinfunction "V_FB_B6") (pintype "bidirectional"))
    )
    (net (code "41") (name "OK1E1") (class "Default")
      (node (ref "OK2") (pin "15") (pinfunction "E1_15") (pintype "bidirectional"))
      (node (ref "R23") (pin "2") (pinfunction "2_2") (pintype "passive"))
      (node (ref "U3") (pin "3") (pinfunction "INPUT1_3") (pintype "bidirectional"))
    )
    (net (code "42") (name "OK1E2") (class "Default")
      (node (ref "OK2") (pin "13") (pinfunction "E2_13") (pintype "bidirectional"))
      (node (ref "R25") (pin "2") (pinfunction "2_2") (pintype "passive"))
      (node (ref "U3") (pin "5") (pinfunction "INPUT2_5") (pintype "bidirectional"))
    )
    (net (code "43") (name "OK1E3") (class "Default")
      (node (ref "OK2") (pin "11") (pinfunction "E3_11") (pintype "bidirectional"))
      (node (ref "R27") (pin "2") (pinfunction "2_2") (pintype "passive"))
      (node (ref "U3") (pin "7") (pinfunction "INPUT3_7") (pintype "bidirectional"))
    )
    (net (code "44") (name "OK1E4") (class "Default")
      (node (ref "OK2") (pin "9") (pinfunction "E4_9") (pintype "bidirectional"))
      (node (ref "R29") (pin "2") (pinfunction "2_2") (pintype "passive"))
      (node (ref "U3") (pin "9") (pinfunction "INPUT4_9") (pintype "bidirectional"))
    )
    (net (code "45") (name "OK2E1") (class "Default")
      (node (ref "OK3") (pin "15") (pinfunction "E1_15") (pintype "bidirectional"))
      (node (ref "R24") (pin "2") (pinfunction "2_2") (pintype "passive"))
      (node (ref "U4") (pin "3") (pinfunction "INPUT1_3") (pintype "bidirectional"))
    )
    (net (code "46") (name "OK2E2") (class "Default")
      (node (ref "OK3") (pin "13") (pinfunction "E2_13") (pintype "bidirectional"))
      (node (ref "R26") (pin "2") (pinfunction "2_2") (pintype "passive"))
      (node (ref "U4") (pin "5") (pinfunction "INPUT2_5") (pintype "bidirectional"))
    )
    (net (code "47") (name "OK2E3") (class "Default")
      (node (ref "OK3") (pin "11") (pinfunction "E3_11") (pintype "bidirectional"))
      (node (ref "R28") (pin "2") (pinfunction "2_2") (pintype "passive"))
      (node (ref "U4") (pin "7") (pinfunction "INPUT3_7") (pintype "bidirectional"))
    )
    (net (code "48") (name "OK2E4") (class "Default")
      (node (ref "OK3") (pin "9") (pinfunction "E4_9") (pintype "bidirectional"))
      (node (ref "R30") (pin "2") (pinfunction "2_2") (pintype "passive"))
      (node (ref "U4") (pin "9") (pinfunction "INPUT4_9") (pintype "bidirectional"))
    )
    (net (code "49") (name "P3") (class "Default")
      (node (ref "J9") (pin "17") (pinfunction "VCC3V_17") (pintype "bidirectional"))
      (node (ref "J9") (pin "47") (pinfunction "VCC3V_47") (pintype "bidirectional"))
      (node (ref "R5") (pin "1") (pinfunction "1_1") (pintype "passive"))
      (node (ref "SJ2") (pin "2") (pinfunction "2_2") (pintype "passive"))
    )
    (net (code "50") (name "P3_SW") (class "Default")
      (node (ref "J2") (pin "4") (pinfunction "4_4") (pintype "bidirectional"))
      (node (ref "J3") (pin "2") (pinfunction "2_2") (pintype "bidirectional"))
      (node (ref "SJ2") (pin "1") (pinfunction "1_1") (pintype "passive"))
    )
    (net (code "51") (name "P18_SW1") (class "Default")
      (node (ref "OK2") (pin "1") (pinfunction "A1_1") (pintype "bidirectional"))
      (node (ref "R7") (pin "1") (pinfunction "1_1") (pintype "passive"))
    )
    (net (code "52") (name "P18_SW2") (class "Default")
      (node (ref "OK2") (pin "5") (pinfunction "A3_5") (pintype "bidirectional"))
      (node (ref "R8") (pin "1") (pinfunction "1_1") (pintype "passive"))
    )
    (net (code "53") (name "P18_SW3") (class "Default")
      (node (ref "OK3") (pin "1") (pinfunction "A1_1") (pintype "bidirectional"))
      (node (ref "R9") (pin "1") (pinfunction "1_1") (pintype "passive"))
    )
    (net (code "54") (name "P18_SW4") (class "Default")
      (node (ref "OK3") (pin "5") (pinfunction "A3_5") (pintype "bidirectional"))
      (node (ref "R10") (pin "1") (pinfunction "1_1") (pintype "passive"))
    )
    (net (code "55") (name "P18_SW5") (class "Default")
      (node (ref "OK2") (pin "3") (pinfunction "A2_3") (pintype "bidirectional"))
      (node (ref "R11") (pin "1") (pinfunction "1_1") (pintype "passive"))
    )
    (net (code "56") (name "P18_SW6") (class "Default")
      (node (ref "OK2") (pin "7") (pinfunction "A4_7") (pintype "bidirectional"))
      (node (ref "R12") (pin "1") (pinfunction "1_1") (pintype "passive"))
    )
    (net (code "57") (name "P18_SW7") (class "Default")
      (node (ref "OK3") (pin "3") (pinfunction "A2_3") (pintype "bidirectional"))
      (node (ref "R13") (pin "1") (pinfunction "1_1") (pintype "passive"))
    )
    (net (code "58") (name "P18_SW8") (class "Default")
      (node (ref "OK3") (pin "7") (pinfunction "A4_7") (pintype "bidirectional"))
      (node (ref "R14") (pin "1") (pinfunction "1_1") (pintype "passive"))
    )
    (net (code "59") (name "PBATT_SW") (class "Default")
      (node (ref "J2") (pin "5") (pinfunction "5_5") (pintype "bidirectional"))
      (node (ref "SJ1") (pin "1") (pinfunction "1_1") (pintype "passive"))
    )
    (net (code "60") (name "PGND") (class "Default")
      (node (ref "C3") (pin "2") (pinfunction "2_2") (pintype "passive"))
      (node (ref "C4") (pin "2") (pinfunction "2_2") (pintype "passive"))
      (node (ref "C5") (pin "K1") (pinfunction "K_K1") (pintype "passive"))
      (node (ref "J3") (pin "1") (pinfunction "1_1") (pintype "bidirectional"))
      (node (ref "J3") (pin "6") (pinfunction "6_6") (pintype "bidirectional"))
      (node (ref "J4") (pin "1") (pinfunction "1_1") (pintype "bidirectional"))
      (node (ref "J4") (pin "4") (pinfunction "4_4") (pintype "bidirectional"))
      (node (ref "J5") (pin "1") (pinfunction "1_1") (pintype "bidirectional"))
      (node (ref "J5") (pin "4") (pinfunction "4_4") (pintype "bidirectional"))
      (node (ref "OK1") (pin "15") (pinfunction "E1_15") (pintype "bidirectional"))
      (node (ref "R23") (pin "1") (pinfunction "1_1") (pintype "passive"))
      (node (ref "R24") (pin "1") (pinfunction "1_1") (pintype "passive"))
      (node (ref "R25") (pin "1") (pinfunction "1_1") (pintype "passive"))
      (node (ref "R26") (pin "1") (pinfunction "1_1") (pintype "passive"))
      (node (ref "R27") (pin "1") (pinfunction "1_1") (pintype "passive"))
      (node (ref "R28") (pin "1") (pinfunction "1_1") (pintype "passive"))
      (node (ref "R29") (pin "1") (pinfunction "1_1") (pintype "passive"))
      (node (ref "R3") (pin "2") (pinfunction "2_2") (pintype "passive"))
      (node (ref "R30") (pin "1") (pinfunction "1_1") (pintype "passive"))
      (node (ref "R36") (pin "2") (pinfunction "2_2") (pintype "passive"))
      (node (ref "R4") (pin "1") (pinfunction "1_1") (pintype "passive"))
      (node (ref "SJ3") (pin "1") (pinfunction "1_1") (pintype "passive"))
      (node (ref "U1") (pin "A1") (pinfunction "PGND_A1") (pintype "bidirectional"))
      (node (ref "U1") (pin "A11") (pinfunction "PGND_A11") (pintype "bidirectional"))
      (node (ref "U1") (pin "A12") (pinfunction "PGND_A12") (pintype "bidirectional"))
      (node (ref "U1") (pin "A2") (pinfunction "PGND_A2") (pintype "bidirectional"))
      (node (ref "U1") (pin "A3") (pinfunction "PGND_A3") (pintype "bidirectional"))
      (node (ref "U1") (pin "A5") (pinfunction "SENSE-_A5") (pintype "bidirectional"))
      (node (ref "U1") (pin "B1") (pinfunction "PGND_B1") (pintype "bidirectional"))
      (node (ref "U1") (pin "B10") (pinfunction "PGND_B10") (pintype "bidirectional"))
      (node (ref "U1") (pin "B11") (pinfunction "PGND_B11") (pintype "bidirectional"))
      (node (ref "U1") (pin "B12") (pinfunction "PGND_B12") (pintype "bidirectional"))
      (node (ref "U1") (pin "B2") (pinfunction "PGND_B2") (pintype "bidirectional"))
      (node (ref "U1") (pin "B3") (pinfunction "PGND_B3") (pintype "bidirectional"))
      (node (ref "U1") (pin "B4") (pinfunction "PGND_B4") (pintype "bidirectional"))
      (node (ref "U1") (pin "C1") (pinfunction "PGND_C1") (pintype "bidirectional"))
      (node (ref "U1") (pin "C10") (pinfunction "PGND_C10") (pintype "bidirectional"))
      (node (ref "U1") (pin "C11") (pinfunction "PGND_C11") (pintype "bidirectional"))
      (node (ref "U1") (pin "C12") (pinfunction "PGND_C12") (pintype "bidirectional"))
      (node (ref "U1") (pin "C2") (pinfunction "PGND_C2") (pintype "bidirectional"))
      (node (ref "U1") (pin "C3") (pinfunction "PGND_C3") (pintype "bidirectional"))
      (node (ref "U1") (pin "C4") (pinfunction "PGND_C4") (pintype "bidirectional"))
      (node (ref "U1") (pin "C5") (pinfunction "PGND_C5") (pintype "bidirectional"))
      (node (ref "U1") (pin "C6") (pinfunction "PGND_C6") (pintype "bidirectional"))
      (node (ref "U1") (pin "C7") (pinfunction "PGND_C7") (pintype "bidirectional"))
      (node (ref "U1") (pin "C8") (pinfunction "PGND_C8") (pintype "bidirectional"))
      (node (ref "U1") (pin "C9") (pinfunction "PGND_C9") (pintype "bidirectional"))
      (node (ref "U1") (pin "D1") (pinfunction "PGND_D1") (pintype "bidirectional"))
      (node (ref "U1") (pin "D10") (pinfunction "PGND_D10") (pintype "bidirectional"))
      (node (ref "U1") (pin "D11") (pinfunction "PGND_D11") (pintype "bidirectional"))
      (node (ref "U1") (pin "D12") (pinfunction "PGND_D12") (pintype "bidirectional"))
      (node (ref "U1") (pin "D2") (pinfunction "PGND_D2") (pintype "bidirectional"))
      (node (ref "U1") (pin "D3") (pinfunction "PGND_D3") (pintype "bidirectional"))
      (node (ref "U1") (pin "D4") (pinfunction "PGND_D4") (pintype "bidirectional"))
      (node (ref "U1") (pin "D5") (pinfunction "PGND_D5") (pintype "bidirectional"))
      (node (ref "U1") (pin "D6") (pinfunction "PGND_D6") (pintype "bidirectional"))
      (node (ref "U1") (pin "D7") (pinfunction "PGND_D7") (pintype "bidirectional"))
      (node (ref "U1") (pin "D8") (pinfunction "PGND_D8") (pintype "bidirectional"))
      (node (ref "U1") (pin "D9") (pinfunction "PGND_D9") (pintype "bidirectional"))
      (node (ref "U1") (pin "E10") (pinfunction "PGND_E10") (pintype "bidirectional"))
      (node (ref "U1") (pin "E11") (pinfunction "PGND_E11") (pintype "bidirectional"))
      (node (ref "U1") (pin "E12") (pinfunction "PGND_E12") (pintype "bidirectional"))
      (node (ref "U1") (pin "E3") (pinfunction "PGND_E3") (pintype "bidirectional"))
      (node (ref "U1") (pin "E4") (pinfunction "PGND_E4") (pintype "bidirectional"))
      (node (ref "U1") (pin "E5") (pinfunction "PGND_E5") (pintype "bidirectional"))
      (node (ref "U1") (pin "E6") (pinfunction "PGND_E6") (pintype "bidirectional"))
      (node (ref "U1") (pin "E7") (pinfunction "PGND_E7") (pintype "bidirectional"))
      (node (ref "U1") (pin "E8") (pinfunction "PGND_E8") (pintype "bidirectional"))
      (node (ref "U1") (pin "E9") (pinfunction "PGND_E9") (pintype "bidirectional"))
      (node (ref "U3") (pin "1") (pinfunction "GND_1") (pintype "bidirectional"))
      (node (ref "U3") (pin "10") (pinfunction "GND_10") (pintype "bidirectional"))
      (node (ref "U4") (pin "1") (pinfunction "GND_1") (pintype "bidirectional"))
      (node (ref "U4") (pin "10") (pinfunction "GND_10") (pintype "bidirectional"))
    )
    (net (code "61") (name "PGOOD_PMA") (class "Default")
      (node (ref "J3") (pin "4") (pinfunction "4_4") (pintype "bidirectional"))
      (node (ref "U1") (pin "B5") (pinfunction "PGOOD_B5") (pintype "bidirectional"))
    )
    (net (code "62") (name "RSENSE") (class "Default")
      (node (ref "R3") (pin "1") (pinfunction "1_1") (pintype "passive"))
      (node (ref "U1") (pin "A4") (pinfunction "SENSE+_A4") (pintype "bidirectional"))
      (node (ref "U1") (pin "F10") (pinfunction "R_SENSE_F10") (pintype "bidirectional"))
      (node (ref "U1") (pin "F11") (pinfunction "R_SENSE_F11") (pintype "bidirectional"))
      (node (ref "U1") (pin "F12") (pinfunction "R_SENSE_F12") (pintype "bidirectional"))
      (node (ref "U1") (pin "G10") (pinfunction "R_SENSE_G10") (pintype "bidirectional"))
      (node (ref "U1") (pin "G11") (pinfunction "R_SENSE_G11") (pintype "bidirectional"))
      (node (ref "U1") (pin "G12") (pinfunction "R_SENSE_G12") (pintype "bidirectional"))
      (node (ref "U1") (pin "G5") (pinfunction "R_SENSE_G5") (pintype "bidirectional"))
      (node (ref "U1") (pin "G6") (pinfunction "R_SENSE_G6") (pintype "bidirectional"))
      (node (ref "U1") (pin "G7") (pinfunction "R_SENSE_G7") (pintype "bidirectional"))
      (node (ref "U1") (pin "G8") (pinfunction "R_SENSE_G8") (pintype "bidirectional"))
      (node (ref "U1") (pin "G9") (pinfunction "R_SENSE_G9") (pintype "bidirectional"))
      (node (ref "U1") (pin "H10") (pinfunction "R_SENSE_H10") (pintype "bidirectional"))
      (node (ref "U1") (pin "H11") (pinfunction "R_SENSE_H11") (pintype "bidirectional"))
      (node (ref "U1") (pin "H12") (pinfunction "R_SENSE_H12") (pintype "bidirectional"))
      (node (ref "U1") (pin "H5") (pinfunction "R_SENSE_H5") (pintype "bidirectional"))
      (node (ref "U1") (pin "H6") (pinfunction "R_SENSE_H6") (pintype "bidirectional"))
      (node (ref "U1") (pin "H7") (pinfunction "R_SENSE_H7") (pintype "bidirectional"))
      (node (ref "U1") (pin "H8") (pinfunction "R_SENSE_H8") (pintype "bidirectional"))
      (node (ref "U1") (pin "H9") (pinfunction "R_SENSE_H9") (pintype "bidirectional"))
      (node (ref "U1") (pin "J5") (pinfunction "R_SENSE_J5") (pintype "bidirectional"))
      (node (ref "U1") (pin "J6") (pinfunction "R_SENSE_J6") (pintype "bidirectional"))
      (node (ref "U1") (pin "J7") (pinfunction "R_SENSE_J7") (pintype "bidirectional"))
      (node (ref "U1") (pin "K5") (pinfunction "R_SENSE_K5") (pintype "bidirectional"))
      (node (ref "U1") (pin "K6") (pinfunction "R_SENSE_K6") (pintype "bidirectional"))
      (node (ref "U1") (pin "L5") (pinfunction "R_SENSE_L5") (pintype "bidirectional"))
      (node (ref "U1") (pin "L6") (pinfunction "R_SENSE_L6") (pintype "bidirectional"))
      (node (ref "U1") (pin "M5") (pinfunction "R_SENSE_M5") (pintype "bidirectional"))
      (node (ref "U1") (pin "M6") (pinfunction "R_SENSE_M6") (pintype "bidirectional"))
    )
    (net (code "63") (name "SGND") (class "Default")
      (node (ref "R2") (pin "2") (pinfunction "2_2") (pintype "passive"))
      (node (ref "SJ3") (pin "2") (pinfunction "2_2") (pintype "passive"))
      (node (ref "SJ4") (pin "2") (pinfunction "2_2") (pintype "passive"))
      (node (ref "U1") (pin "A7") (pinfunction "SGND_A7") (pintype "bidirectional"))
    )
    (net (code "64") (name "SW_P18H1") (class "Default")
      (node (ref "J9") (pin "35") (pinfunction "SDHC_DAT0_35") (pintype "bidirectional"))
      (node (ref "R11") (pin "2") (pinfunction "2_2") (pintype "passive"))
    )
    (net (code "65") (name "SW_P18H2") (class "Default")
      (node (ref "J9") (pin "34") (pinfunction "UART1_TX_34") (pintype "bidirectional"))
      (node (ref "R12") (pin "2") (pinfunction "2_2") (pintype "passive"))
    )
    (net (code "66") (name "SW_P18H3") (class "Default")
      (node (ref "J9") (pin "33") (pinfunction "SDHC_CMD_33") (pintype "bidirectional"))
      (node (ref "R13") (pin "2") (pinfunction "2_2") (pintype "passive"))
    )
    (net (code "67") (name "SW_P18H4") (class "Default")
      (node (ref "J9") (pin "32") (pinfunction "UART1_RX_32") (pintype "bidirectional"))
      (node (ref "R14") (pin "2") (pinfunction "2_2") (pintype "passive"))
    )
    (net (code "68") (name "SW_P18L1") (class "Default")
      (node (ref "J9") (pin "39") (pinfunction "SDHC_DAT2_39") (pintype "bidirectional"))
      (node (ref "R7") (pin "2") (pinfunction "2_2") (pintype "passive"))
    )
    (net (code "69") (name "SW_P18L2") (class "Default")
      (node (ref "J9") (pin "38") (pinfunction "UART1_CTS_38") (pintype "bidirectional"))
      (node (ref "R8") (pin "2") (pinfunction "2_2") (pintype "passive"))
    )
    (net (code "70") (name "SW_P18L3") (class "Default")
      (node (ref "J9") (pin "37") (pinfunction "SDHC_DAT1_37") (pintype "bidirectional"))
      (node (ref "R9") (pin "2") (pinfunction "2_2") (pintype "passive"))
    )
    (net (code "71") (name "SW_P18L4") (class "Default")
      (node (ref "J9") (pin "36") (pinfunction "UART1_RTS_36") (pintype "bidirectional"))
      (node (ref "R10") (pin "2") (pinfunction "2_2") (pintype "passive"))
    )
    (net (code "72") (name "SW_RUNPMA") (class "Default")
      (node (ref "J9") (pin "23") (pinfunction "T2IN_23") (pintype "bidirectional"))
      (node (ref "U1") (pin "A8") (pinfunction "RUN_A8") (pintype "bidirectional"))
    )
    (net (code "73") (name "SW_TP1") (class "Default")
      (node (ref "J3") (pin "7") (pinfunction "7_7") (pintype "bidirectional"))
      (node (ref "J9") (pin "31") (pinfunction "SDHC_CLK_31") (pintype "bidirectional"))
      (node (ref "OK1") (pin "2") (pinfunction "K1_2") (pintype "bidirectional"))
    )
    (net (code "74") (name "TP1_OUT") (class "Default")
      (node (ref "J3") (pin "8") (pinfunction "8_8") (pintype "bidirectional"))
      (node (ref "J4") (pin "3") (pinfunction "3_3") (pintype "bidirectional"))
      (node (ref "J4") (pin "6") (pinfunction "6_6") (pintype "bidirectional"))
      (node (ref "J5") (pin "3") (pinfunction "3_3") (pintype "bidirectional"))
      (node (ref "J5") (pin "6") (pinfunction "6_6") (pintype "bidirectional"))
      (node (ref "OK1") (pin "16") (pinfunction "C1_16") (pintype "bidirectional"))
      (node (ref "R35") (pin "2") (pinfunction "2_2") (pintype "passive"))
      (node (ref "R36") (pin "1") (pinfunction "1_1") (pintype "passive"))
    )
    (net (code "75") (name "UART0_RX") (class "Default")
      (node (ref "J2") (pin "6") (pinfunction "6_6") (pintype "bidirectional"))
      (node (ref "J6") (pin "3") (pinfunction "3_3") (pintype "bidirectional"))
      (node (ref "J9") (pin "24") (pinfunction "UART0_RX_24") (pintype "bidirectional"))
    )
    (net (code "76") (name "UART0_TX") (class "Default")
      (node (ref "J2") (pin "3") (pinfunction "3_3") (pintype "bidirectional"))
      (node (ref "J6") (pin "2") (pinfunction "2_2") (pintype "bidirectional"))
      (node (ref "J9") (pin "26") (pinfunction "UART0_TX_26") (pintype "bidirectional"))
    )
    (net (code "77") (name "VBATT_IN") (class "Default")
      (node (ref "C1") (pin "A1") (pinfunction "A_A1") (pintype "passive"))
      (node (ref "J3") (pin "3") (pinfunction "3_3") (pintype "bidirectional"))
      (node (ref "L1") (pin "1") (pinfunction "1_1") (pintype "bidirectional"))
      (node (ref "SJ1") (pin "2") (pinfunction "2_2") (pintype "passive"))
    )
    (net (code "78") (name "VIN") (class "Default")
      (node (ref "C2") (pin "1") (pinfunction "1_1") (pintype "passive"))
      (node (ref "L1") (pin "2") (pinfunction "2_2") (pintype "bidirectional"))
      (node (ref "U1") (pin "J10") (pinfunction "V_IN_J10") (pintype "bidirectional"))
      (node (ref "U1") (pin "J11") (pinfunction "V_IN_J11") (pintype "bidirectional"))
      (node (ref "U1") (pin "J12") (pinfunction "V_IN_J12") (pintype "bidirectional"))
      (node (ref "U1") (pin "K10") (pinfunction "V_IN_K10") (pintype "bidirectional"))
      (node (ref "U1") (pin "K11") (pinfunction "V_IN_K11") (pintype "bidirectional"))
      (node (ref "U1") (pin "K12") (pinfunction "V_IN_K12") (pintype "bidirectional"))
      (node (ref "U1") (pin "L10") (pinfunction "V_IN_L10") (pintype "bidirectional"))
      (node (ref "U1") (pin "L11") (pinfunction "V_IN_L11") (pintype "bidirectional"))
      (node (ref "U1") (pin "L12") (pinfunction "V_IN_L12") (pintype "bidirectional"))
      (node (ref "U1") (pin "M10") (pinfunction "V_IN_M10") (pintype "bidirectional"))
      (node (ref "U1") (pin "M11") (pinfunction "V_IN_M11") (pintype "bidirectional"))
      (node (ref "U1") (pin "M12") (pinfunction "V_IN_M12") (pintype "bidirectional"))
    )
    (net (code "79") (name "VOUT") (class "Default")
      (node (ref "C3") (pin "1") (pinfunction "1_1") (pintype "passive"))
      (node (ref "C4") (pin "1") (pinfunction "1_1") (pintype "passive"))
      (node (ref "L3") (pin "1") (pinfunction "1_1") (pintype "bidirectional"))
      (node (ref "U1") (pin "E1") (pinfunction "V_OUT_E1") (pintype "bidirectional"))
      (node (ref "U1") (pin "E2") (pinfunction "V_OUT_E2") (pintype "bidirectional"))
      (node (ref "U1") (pin "F1") (pinfunction "V_OUT_F1") (pintype "bidirectional"))
      (node (ref "U1") (pin "F2") (pinfunction "V_OUT_F2") (pintype "bidirectional"))
      (node (ref "U1") (pin "F3") (pinfunction "V_OUT_F3") (pintype "bidirectional"))
      (node (ref "U1") (pin "F4") (pinfunction "V_OUT_F4") (pintype "bidirectional"))
      (node (ref "U1") (pin "G1") (pinfunction "V_OUT_G1") (pintype "bidirectional"))
      (node (ref "U1") (pin "G2") (pinfunction "V_OUT_G2") (pintype "bidirectional"))
      (node (ref "U1") (pin "G3") (pinfunction "V_OUT_G3") (pintype "bidirectional"))
      (node (ref "U1") (pin "G4") (pinfunction "V_OUT_G4") (pintype "bidirectional"))
      (node (ref "U1") (pin "H2") (pinfunction "V_OUT_H2") (pintype "bidirectional"))
      (node (ref "U1") (pin "H3") (pinfunction "V_OUT_H3") (pintype "bidirectional"))
      (node (ref "U1") (pin "H4") (pinfunction "V_OUT_H4") (pintype "bidirectional"))
      (node (ref "U1") (pin "VOUT") (pinfunction "V_OUT_VOUT") (pintype "bidirectional"))
    )
    (net (code "80") (name "VOUTA") (class "Default")
      (node (ref "C5") (pin "A1") (pinfunction "A_A1") (pintype "passive"))
      (node (ref "J3") (pin "5") (pinfunction "5_5") (pintype "bidirectional"))
      (node (ref "L3") (pin "2") (pinfunction "2_2") (pintype "bidirectional"))
      (node (ref "Q1") (pin "D") (pinfunction "D_D") (pintype "bidirectional"))
      (node (ref "Q3") (pin "D") (pinfunction "D_D") (pintype "bidirectional"))
      (node (ref "Q5") (pin "D") (pinfunction "D_D") (pintype "bidirectional"))
      (node (ref "Q7") (pin "D") (pinfunction "D_D") (pintype "bidirectional"))
      (node (ref "R15") (pin "1") (pinfunction "1_1") (pintype "passive"))
      (node (ref "R16") (pin "1") (pinfunction "1_1") (pintype "passive"))
      (node (ref "R17") (pin "1") (pinfunction "1_1") (pintype "passive"))
      (node (ref "R18") (pin "1") (pinfunction "1_1") (pintype "passive"))
      (node (ref "R19") (pin "1") (pinfunction "1_1") (pintype "passive"))
      (node (ref "R20") (pin "1") (pinfunction "1_1") (pintype "passive"))
      (node (ref "R21") (pin "1") (pinfunction "1_1") (pintype "passive"))
      (node (ref "R22") (pin "1") (pinfunction "1_1") (pintype "passive"))
      (node (ref "R31") (pin "2") (pinfunction "2_2") (pintype "passive"))
      (node (ref "R32") (pin "2") (pinfunction "2_2") (pintype "passive"))
      (node (ref "R33") (pin "2") (pinfunction "2_2") (pintype "passive"))
      (node (ref "R34") (pin "2") (pinfunction "2_2") (pintype "passive"))
      (node (ref "R35") (pin "1") (pinfunction "1_1") (pintype "passive"))
      (node (ref "U3") (pin "11") (pinfunction "V+_11") (pintype "bidirectional"))
      (node (ref "U3") (pin "13") (pinfunction "SENSE4_13") (pintype "bidirectional"))
      (node (ref "U3") (pin "15") (pinfunction "SENSE3_15") (pintype "bidirectional"))
      (node (ref "U3") (pin "17") (pinfunction "SENSE2_17") (pintype "bidirectional"))
      (node (ref "U3") (pin "19") (pinfunction "SENSE1_19") (pintype "bidirectional"))
      (node (ref "U3") (pin "20") (pinfunction "V+_20") (pintype "bidirectional"))
      (node (ref "U4") (pin "11") (pinfunction "V+_11") (pintype "bidirectional"))
      (node (ref "U4") (pin "13") (pinfunction "SENSE4_13") (pintype "bidirectional"))
      (node (ref "U4") (pin "15") (pinfunction "SENSE3_15") (pintype "bidirectional"))
      (node (ref "U4") (pin "17") (pinfunction "SENSE2_17") (pintype "bidirectional"))
      (node (ref "U4") (pin "19") (pinfunction "SENSE1_19") (pintype "bidirectional"))
      (node (ref "U4") (pin "20") (pinfunction "V+_20") (pintype "bidirectional"))
    )
    (net (code "81") (name "unconnected-(J1-+5V_SW-Pad33)") (class "Default")
      (node (ref "J1") (pin "33") (pinfunction "+5V_SW_33") (pintype "bidirectional"))
    )
    (net (code "82") (name "unconnected-(J1-+5V_SYS-Pad77)") (class "Default")
      (node (ref "J1") (pin "77") (pinfunction "+5V_SYS_77") (pintype "bidirectional"))
    )
    (net (code "83") (name "unconnected-(J1-+5V_SYS-Pad78)") (class "Default")
      (node (ref "J1") (pin "78") (pinfunction "+5V_SYS_78") (pintype "bidirectional"))
    )
    (net (code "84") (name "unconnected-(J1-+5V_USB-Pad32)") (class "Default")
      (node (ref "J1") (pin "32") (pinfunction "+5V_USB_32") (pintype "bidirectional"))
    )
    (net (code "85") (name "unconnected-(J1--CTS_MHX-Pad35)") (class "Default")
      (node (ref "J1") (pin "35") (pinfunction "-CTS_MHX_35") (pintype "bidirectional"))
    )
    (net (code "86") (name "unconnected-(J1--DSR_MHX-Pad37)") (class "Default")
      (node (ref "J1") (pin "37") (pinfunction "-DSR_MHX_37") (pintype "bidirectional"))
    )
    (net (code "87") (name "unconnected-(J1--DTR_MHX-Pad38)") (class "Default")
      (node (ref "J1") (pin "38") (pinfunction "-DTR_MHX_38") (pintype "bidirectional"))
    )
    (net (code "88") (name "unconnected-(J1--FAULT-Pad25)") (class "Default")
      (node (ref "J1") (pin "25") (pinfunction "-FAULT_25") (pintype "bidirectional"))
    )
    (net (code "89") (name "unconnected-(J1--RESET-Pad29)") (class "Default")
      (node (ref "J1") (pin "29") (pinfunction "-RESET_29") (pintype "bidirectional"))
    )
    (net (code "90") (name "unconnected-(J1--RST_MHX-Pad34)") (class "Default")
      (node (ref "J1") (pin "34") (pinfunction "-RST_MHX_34") (pintype "bidirectional"))
    )
    (net (code "91") (name "unconnected-(J1--RTS_MHX-Pad36)") (class "Default")
      (node (ref "J1") (pin "36") (pinfunction "-RTS_MHX_36") (pintype "bidirectional"))
    )
    (net (code "92") (name "unconnected-(J1-OFF_VCC-Pad31)") (class "Default")
      (node (ref "J1") (pin "31") (pinfunction "OFF_VCC_31") (pintype "bidirectional"))
    )
    (net (code "93") (name "unconnected-(J1-P1.0-Pad68)") (class "Default")
      (node (ref "J1") (pin "68") (pinfunction "P1.0_68") (pintype "bidirectional"))
    )
    (net (code "94") (name "unconnected-(J1-P1.1-Pad67)") (class "Default")
      (node (ref "J1") (pin "67") (pinfunction "P1.1_67") (pintype "bidirectional"))
    )
    (net (code "95") (name "unconnected-(J1-P1.2-Pad66)") (class "Default")
      (node (ref "J1") (pin "66") (pinfunction "P1.2_66") (pintype "bidirectional"))
    )
    (net (code "96") (name "unconnected-(J1-P1.3-Pad65)") (class "Default")
      (node (ref "J1") (pin "65") (pinfunction "P1.3_65") (pintype "bidirectional"))
    )
    (net (code "97") (name "unconnected-(J1-P1.4-Pad64)") (class "Default")
      (node (ref "J1") (pin "64") (pinfunction "P1.4_64") (pintype "bidirectional"))
    )
    (net (code "98") (name "unconnected-(J1-P1.5-Pad63)") (class "Default")
      (node (ref "J1") (pin "63") (pinfunction "P1.5_63") (pintype "bidirectional"))
    )
    (net (code "99") (name "unconnected-(J1-P1.6-Pad62)") (class "Default")
      (node (ref "J1") (pin "62") (pinfunction "P1.6_62") (pintype "bidirectional"))
    )
    (net (code "100") (name "unconnected-(J1-P1.7-Pad61)") (class "Default")
      (node (ref "J1") (pin "61") (pinfunction "P1.7_61") (pintype "bidirectional"))
    )
    (net (code "101") (name "unconnected-(J1-P2.0-Pad76)") (class "Default")
      (node (ref "J1") (pin "76") (pinfunction "P2.0_76") (pintype "bidirectional"))
    )
    (net (code "102") (name "unconnected-(J1-P2.1-Pad75)") (class "Default")
      (node (ref "J1") (pin "75") (pinfunction "P2.1_75") (pintype "bidirectional"))
    )
    (net (code "103") (name "unconnected-(J1-P2.2-Pad74)") (class "Default")
      (node (ref "J1") (pin "74") (pinfunction "P2.2_74") (pintype "bidirectional"))
    )
    (net (code "104") (name "unconnected-(J1-P2.3-Pad73)") (class "Default")
      (node (ref "J1") (pin "73") (pinfunction "P2.3_73") (pintype "bidirectional"))
    )
    (net (code "105") (name "unconnected-(J1-P2.4-Pad72)") (class "Default")
      (node (ref "J1") (pin "72") (pinfunction "P2.4_72") (pintype "bidirectional"))
    )
    (net (code "106") (name "unconnected-(J1-P2.5-Pad71)") (class "Default")
      (node (ref "J1") (pin "71") (pinfunction "P2.5_71") (pintype "bidirectional"))
    )
    (net (code "107") (name "unconnected-(J1-P2.6-Pad70)") (class "Default")
      (node (ref "J1") (pin "70") (pinfunction "P2.6_70") (pintype "bidirectional"))
    )
    (net (code "108") (name "unconnected-(J1-P2.7-Pad69)") (class "Default")
      (node (ref "J1") (pin "69") (pinfunction "P2.7_69") (pintype "bidirectional"))
    )
    (net (code "109") (name "unconnected-(J1-P3.0-Pad24)") (class "Default")
      (node (ref "J1") (pin "24") (pinfunction "P3.0_24") (pintype "bidirectional"))
    )
    (net (code "110") (name "unconnected-(J1-P3.1-Pad23)") (class "Default")
      (node (ref "J1") (pin "23") (pinfunction "P3.1_23") (pintype "bidirectional"))
    )
    (net (code "111") (name "unconnected-(J1-P3.2-Pad22)") (class "Default")
      (node (ref "J1") (pin "22") (pinfunction "P3.2_22") (pintype "bidirectional"))
    )
    (net (code "112") (name "unconnected-(J1-P3.3-Pad21)") (class "Default")
      (node (ref "J1") (pin "21") (pinfunction "P3.3_21") (pintype "bidirectional"))
    )
    (net (code "113") (name "unconnected-(J1-P3.4-Pad20)") (class "Default")
      (node (ref "J1") (pin "20") (pinfunction "P3.4_20") (pintype "bidirectional"))
    )
    (net (code "114") (name "unconnected-(J1-P3.5-Pad19)") (class "Default")
      (node (ref "J1") (pin "19") (pinfunction "P3.5_19") (pintype "bidirectional"))
    )
    (net (code "115") (name "unconnected-(J1-P3.6-Pad18)") (class "Default")
      (node (ref "J1") (pin "18") (pinfunction "P3.6_18") (pintype "bidirectional"))
    )
    (net (code "116") (name "unconnected-(J1-P3.7-Pad17)") (class "Default")
      (node (ref "J1") (pin "17") (pinfunction "P3.7_17") (pintype "bidirectional"))
    )
    (net (code "117") (name "unconnected-(J1-P4.0-Pad16)") (class "Default")
      (node (ref "J1") (pin "16") (pinfunction "P4.0_16") (pintype "bidirectional"))
    )
    (net (code "118") (name "unconnected-(J1-P4.1-Pad15)") (class "Default")
      (node (ref "J1") (pin "15") (pinfunction "P4.1_15") (pintype "bidirectional"))
    )
    (net (code "119") (name "unconnected-(J1-P4.2-Pad14)") (class "Default")
      (node (ref "J1") (pin "14") (pinfunction "P4.2_14") (pintype "bidirectional"))
    )
    (net (code "120") (name "unconnected-(J1-P4.3-Pad13)") (class "Default")
      (node (ref "J1") (pin "13") (pinfunction "P4.3_13") (pintype "bidirectional"))
    )
    (net (code "121") (name "unconnected-(J1-P4.4-Pad12)") (class "Default")
      (node (ref "J1") (pin "12") (pinfunction "P4.4_12") (pintype "bidirectional"))
    )
    (net (code "122") (name "unconnected-(J1-P4.5-Pad11)") (class "Default")
      (node (ref "J1") (pin "11") (pinfunction "P4.5_11") (pintype "bidirectional"))
    )
    (net (code "123") (name "unconnected-(J1-P4.6-Pad10)") (class "Default")
      (node (ref "J1") (pin "10") (pinfunction "P4.6_10") (pintype "bidirectional"))
    )
    (net (code "124") (name "unconnected-(J1-P4.7-Pad9)") (class "Default")
      (node (ref "J1") (pin "9") (pinfunction "P4.7_9") (pintype "bidirectional"))
    )
    (net (code "125") (name "unconnected-(J1-P5.0-Pad8)") (class "Default")
      (node (ref "J1") (pin "8") (pinfunction "P5.0_8") (pintype "bidirectional"))
    )
    (net (code "126") (name "unconnected-(J1-P5.1-Pad7)") (class "Default")
      (node (ref "J1") (pin "7") (pinfunction "P5.1_7") (pintype "bidirectional"))
    )
    (net (code "127") (name "unconnected-(J1-P5.2-Pad6)") (class "Default")
      (node (ref "J1") (pin "6") (pinfunction "P5.2_6") (pintype "bidirectional"))
    )
    (net (code "128") (name "unconnected-(J1-P5.3-Pad5)") (class "Default")
      (node (ref "J1") (pin "5") (pinfunction "P5.3_5") (pintype "bidirectional"))
    )
    (net (code "129") (name "unconnected-(J1-P5.4-Pad4)") (class "Default")
      (node (ref "J1") (pin "4") (pinfunction "P5.4_4") (pintype "bidirectional"))
    )
    (net (code "130") (name "unconnected-(J1-P5.5-Pad3)") (class "Default")
      (node (ref "J1") (pin "3") (pinfunction "P5.5_3") (pintype "bidirectional"))
    )
    (net (code "131") (name "unconnected-(J1-P5.6-Pad2)") (class "Default")
      (node (ref "J1") (pin "2") (pinfunction "P5.6_2") (pintype "bidirectional"))
    )
    (net (code "132") (name "unconnected-(J1-P5.7-Pad1)") (class "Default")
      (node (ref "J1") (pin "1") (pinfunction "P5.7_1") (pintype "bidirectional"))
    )
    (net (code "133") (name "unconnected-(J1-P6.0-Pad60)") (class "Default")
      (node (ref "J1") (pin "60") (pinfunction "P6.0_60") (pintype "bidirectional"))
    )
    (net (code "134") (name "unconnected-(J1-P6.1-Pad59)") (class "Default")
      (node (ref "J1") (pin "59") (pinfunction "P6.1_59") (pintype "bidirectional"))
    )
    (net (code "135") (name "unconnected-(J1-P6.2-Pad58)") (class "Default")
      (node (ref "J1") (pin "58") (pinfunction "P6.2_58") (pintype "bidirectional"))
    )
    (net (code "136") (name "unconnected-(J1-P6.3-Pad57)") (class "Default")
      (node (ref "J1") (pin "57") (pinfunction "P6.3_57") (pintype "bidirectional"))
    )
    (net (code "137") (name "unconnected-(J1-P6.4-Pad56)") (class "Default")
      (node (ref "J1") (pin "56") (pinfunction "P6.4_56") (pintype "bidirectional"))
    )
    (net (code "138") (name "unconnected-(J1-P6.5-Pad55)") (class "Default")
      (node (ref "J1") (pin "55") (pinfunction "P6.5_55") (pintype "bidirectional"))
    )
    (net (code "139") (name "unconnected-(J1-P6.6-Pad54)") (class "Default")
      (node (ref "J1") (pin "54") (pinfunction "P6.6_54") (pintype "bidirectional"))
    )
    (net (code "140") (name "unconnected-(J1-P6.7-Pad53)") (class "Default")
      (node (ref "J1") (pin "53") (pinfunction "P6.7_53") (pintype "bidirectional"))
    )
    (net (code "141") (name "unconnected-(J1-RSVD0-Pad44)") (class "Default")
      (node (ref "J1") (pin "44") (pinfunction "RSVD0_44") (pintype "bidirectional"))
    )
    (net (code "142") (name "unconnected-(J1-RSVD1-Pad45)") (class "Default")
      (node (ref "J1") (pin "45") (pinfunction "RSVD1_45") (pintype "bidirectional"))
    )
    (net (code "143") (name "unconnected-(J1-RSVD2-Pad46)") (class "Default")
      (node (ref "J1") (pin "46") (pinfunction "RSVD2_46") (pintype "bidirectional"))
    )
    (net (code "144") (name "unconnected-(J1-RXD_MHX-Pad40)") (class "Default")
      (node (ref "J1") (pin "40") (pinfunction "RXD_MHX_40") (pintype "bidirectional"))
    )
    (net (code "145") (name "unconnected-(J1-SENSE-Pad27)") (class "Default")
      (node (ref "J1") (pin "27") (pinfunction "SENSE_27") (pintype "bidirectional"))
    )
    (net (code "146") (name "unconnected-(J1-SW0-Pad85)") (class "Default")
      (node (ref "J1") (pin "85") (pinfunction "SW0_85") (pintype "bidirectional"))
    )
    (net (code "147") (name "unconnected-(J1-SW0-Pad86)") (class "Default")
      (node (ref "J1") (pin "86") (pinfunction "SW0_86") (pintype "bidirectional"))
    )
    (net (code "148") (name "unconnected-(J1-SW1-Pad87)") (class "Default")
      (node (ref "J1") (pin "87") (pinfunction "SW1_87") (pintype "bidirectional"))
    )
    (net (code "149") (name "unconnected-(J1-SW1-Pad88)") (class "Default")
      (node (ref "J1") (pin "88") (pinfunction "SW1_88") (pintype "bidirectional"))
    )
    (net (code "150") (name "unconnected-(J1-SW2-Pad89)") (class "Default")
      (node (ref "J1") (pin "89") (pinfunction "SW2_89") (pintype "bidirectional"))
    )
    (net (code "151") (name "unconnected-(J1-SW2-Pad90)") (class "Default")
      (node (ref "J1") (pin "90") (pinfunction "SW2_90") (pintype "bidirectional"))
    )
    (net (code "152") (name "unconnected-(J1-SW3-Pad91)") (class "Default")
      (node (ref "J1") (pin "91") (pinfunction "SW3_91") (pintype "bidirectional"))
    )
    (net (code "153") (name "unconnected-(J1-SW3-Pad92)") (class "Default")
      (node (ref "J1") (pin "92") (pinfunction "SW3_92") (pintype "bidirectional"))
    )
    (net (code "154") (name "unconnected-(J1-SW4-Pad93)") (class "Default")
      (node (ref "J1") (pin "93") (pinfunction "SW4_93") (pintype "bidirectional"))
    )
    (net (code "155") (name "unconnected-(J1-SW4-Pad94)") (class "Default")
      (node (ref "J1") (pin "94") (pinfunction "SW4_94") (pintype "bidirectional"))
    )
    (net (code "156") (name "unconnected-(J1-SW5-Pad95)") (class "Default")
      (node (ref "J1") (pin "95") (pinfunction "SW5_95") (pintype "bidirectional"))
    )
    (net (code "157") (name "unconnected-(J1-SW5-Pad96)") (class "Default")
      (node (ref "J1") (pin "96") (pinfunction "SW5_96") (pintype "bidirectional"))
    )
    (net (code "158") (name "unconnected-(J1-TXD_MHX-Pad39)") (class "Default")
      (node (ref "J1") (pin "39") (pinfunction "TXD_MHX_39") (pintype "bidirectional"))
    )
    (net (code "159") (name "unconnected-(J1-USER0-Pad47)") (class "Default")
      (node (ref "J1") (pin "47") (pinfunction "USER0_47") (pintype "bidirectional"))
    )
    (net (code "160") (name "unconnected-(J1-USER1-Pad48)") (class "Default")
      (node (ref "J1") (pin "48") (pinfunction "USER1_48") (pintype "bidirectional"))
    )
    (net (code "161") (name "unconnected-(J1-USER2-Pad49)") (class "Default")
      (node (ref "J1") (pin "49") (pinfunction "USER2_49") (pintype "bidirectional"))
    )
    (net (code "162") (name "unconnected-(J1-USER3-Pad50)") (class "Default")
      (node (ref "J1") (pin "50") (pinfunction "USER3_50") (pintype "bidirectional"))
    )
    (net (code "163") (name "unconnected-(J1-USER4-Pad51)") (class "Default")
      (node (ref "J1") (pin "51") (pinfunction "USER4_51") (pintype "bidirectional"))
    )
    (net (code "164") (name "unconnected-(J1-USER5-Pad52)") (class "Default")
      (node (ref "J1") (pin "52") (pinfunction "USER5_52") (pintype "bidirectional"))
    )
    (net (code "165") (name "unconnected-(J1-USER6-Pad99)") (class "Default")
      (node (ref "J1") (pin "99") (pinfunction "USER6_99") (pintype "bidirectional"))
    )
    (net (code "166") (name "unconnected-(J1-USER7-Pad100)") (class "Default")
      (node (ref "J1") (pin "100") (pinfunction "USER7_100") (pintype "bidirectional"))
    )
    (net (code "167") (name "unconnected-(J1-USER8-Pad101)") (class "Default")
      (node (ref "J1") (pin "101") (pinfunction "USER8_101") (pintype "bidirectional"))
    )
    (net (code "168") (name "unconnected-(J1-USER9-Pad102)") (class "Default")
      (node (ref "J1") (pin "102") (pinfunction "USER9_102") (pintype "bidirectional"))
    )
    (net (code "169") (name "unconnected-(J1-USER10-Pad103)") (class "Default")
      (node (ref "J1") (pin "103") (pinfunction "USER10_103") (pintype "bidirectional"))
    )
    (net (code "170") (name "unconnected-(J1-USER11-Pad104)") (class "Default")
      (node (ref "J1") (pin "104") (pinfunction "USER11_104") (pintype "bidirectional"))
    )
    (net (code "171") (name "unconnected-(J1-VBACKUP-Pad42)") (class "Default")
      (node (ref "J1") (pin "42") (pinfunction "VBACKUP_42") (pintype "bidirectional"))
    )
    (net (code "172") (name "unconnected-(J1-VBATT-Pad97)") (class "Default")
      (node (ref "J1") (pin "97") (pinfunction "VBATT_97") (pintype "bidirectional"))
    )
    (net (code "173") (name "unconnected-(J1-VBATT-Pad98)") (class "Default")
      (node (ref "J1") (pin "98") (pinfunction "VBATT_98") (pintype "bidirectional"))
    )
    (net (code "174") (name "unconnected-(J1-VCC_SYS-Pad79)") (class "Default")
      (node (ref "J1") (pin "79") (pinfunction "VCC_SYS_79") (pintype "bidirectional"))
    )
    (net (code "175") (name "unconnected-(J1-VCC_SYS-Pad80)") (class "Default")
      (node (ref "J1") (pin "80") (pinfunction "VCC_SYS_80") (pintype "bidirectional"))
    )
    (net (code "176") (name "unconnected-(J1-VEREF+-Pad28)") (class "Default")
      (node (ref "J1") (pin "28") (pinfunction "VEREF+_28") (pintype "bidirectional"))
    )
    (net (code "177") (name "unconnected-(J1-VREF+-Pad26)") (class "Default")
      (node (ref "J1") (pin "26") (pinfunction "VREF+_26") (pintype "bidirectional"))
    )
    (net (code "178") (name "unconnected-(J1-VREF--Pad30)") (class "Default")
      (node (ref "J1") (pin "30") (pinfunction "VREF-_30") (pintype "bidirectional"))
    )
    (net (code "179") (name "unconnected-(J4-Pad2)") (class "Default")
      (node (ref "J4") (pin "2") (pinfunction "2_2") (pintype "bidirectional"))
    )
    (net (code "180") (name "unconnected-(J4-Pad5)") (class "Default")
      (node (ref "J4") (pin "5") (pinfunction "5_5") (pintype "bidirectional"))
    )
    (net (code "181") (name "unconnected-(J4-Pad9)") (class "Default")
      (node (ref "J4") (pin "9") (pinfunction "9_9") (pintype "bidirectional"))
    )
    (net (code "182") (name "unconnected-(J4-Pad12)") (class "Default")
      (node (ref "J4") (pin "12") (pinfunction "12_12") (pintype "bidirectional"))
    )
    (net (code "183") (name "unconnected-(J5-Pad2)") (class "Default")
      (node (ref "J5") (pin "2") (pinfunction "2_2") (pintype "bidirectional"))
    )
    (net (code "184") (name "unconnected-(J5-Pad5)") (class "Default")
      (node (ref "J5") (pin "5") (pinfunction "5_5") (pintype "bidirectional"))
    )
    (net (code "185") (name "unconnected-(J5-Pad9)") (class "Default")
      (node (ref "J5") (pin "9") (pinfunction "9_9") (pintype "bidirectional"))
    )
    (net (code "186") (name "unconnected-(J5-Pad12)") (class "Default")
      (node (ref "J5") (pin "12") (pinfunction "12_12") (pintype "bidirectional"))
    )
    (net (code "187") (name "unconnected-(J9-ADC_IN0-Pad2)") (class "Default")
      (node (ref "J9") (pin "2") (pinfunction "ADC_IN0_2") (pintype "bidirectional"))
    )
    (net (code "188") (name "unconnected-(J9-ADC_IN1-Pad1)") (class "Default")
      (node (ref "J9") (pin "1") (pinfunction "ADC_IN1_1") (pintype "bidirectional"))
    )
    (net (code "189") (name "unconnected-(J9-ADC_IN2-Pad4)") (class "Default")
      (node (ref "J9") (pin "4") (pinfunction "ADC_IN2_4") (pintype "bidirectional"))
    )
    (net (code "190") (name "unconnected-(J9-ADC_IN3-Pad3)") (class "Default")
      (node (ref "J9") (pin "3") (pinfunction "ADC_IN3_3") (pintype "bidirectional"))
    )
    (net (code "191") (name "unconnected-(J9-ADC_IN4-Pad6)") (class "Default")
      (node (ref "J9") (pin "6") (pinfunction "ADC_IN4_6") (pintype "bidirectional"))
    )
    (net (code "192") (name "unconnected-(J9-ADC_IN7-Pad5)") (class "Default")
      (node (ref "J9") (pin "5") (pinfunction "ADC_IN7_5") (pintype "bidirectional"))
    )
    (net (code "193") (name "unconnected-(J9-AGND-Pad8)") (class "Default")
      (node (ref "J9") (pin "8") (pinfunction "AGND_8") (pintype "bidirectional"))
    )
    (net (code "194") (name "unconnected-(J9-CAN1_RX-Pad20)") (class "Default")
      (node (ref "J9") (pin "20") (pinfunction "CAN1_RX_20") (pintype "bidirectional"))
    )
    (net (code "195") (name "unconnected-(J9-CAN1_TX-Pad22)") (class "Default")
      (node (ref "J9") (pin "22") (pinfunction "CAN1_TX_22") (pintype "bidirectional"))
    )
    (net (code "196") (name "unconnected-(J9-ERX_JM-Pad46)") (class "Default")
      (node (ref "J9") (pin "46") (pinfunction "ERX_JM_46") (pintype "bidirectional"))
    )
    (net (code "197") (name "unconnected-(J9-ERX_JP-Pad43)") (class "Default")
      (node (ref "J9") (pin "43") (pinfunction "ERX_JP_43") (pintype "bidirectional"))
    )
    (net (code "198") (name "unconnected-(J9-ETX_JM-Pad44)") (class "Default")
      (node (ref "J9") (pin "44") (pinfunction "ETX_JM_44") (pintype "bidirectional"))
    )
    (net (code "199") (name "unconnected-(J9-ETX_JP-Pad45)") (class "Default")
      (node (ref "J9") (pin "45") (pinfunction "ETX_JP_45") (pintype "bidirectional"))
    )
    (net (code "200") (name "unconnected-(J9-IRQ2-Pad50)") (class "Default")
      (node (ref "J9") (pin "50") (pinfunction "IRQ2_50") (pintype "bidirectional"))
    )
    (net (code "201") (name "unconnected-(J9-IRQ3-Pad49)") (class "Default")
      (node (ref "J9") (pin "49") (pinfunction "IRQ3_49") (pintype "bidirectional"))
    )
    (net (code "202") (name "unconnected-(J9-IRQ7-Pad9)") (class "Default")
      (node (ref "J9") (pin "9") (pinfunction "IRQ7_9") (pintype "bidirectional"))
    )
    (net (code "203") (name "unconnected-(J9-LINKLED-Pad42)") (class "Default")
      (node (ref "J9") (pin "42") (pinfunction "LINKLED_42") (pintype "bidirectional"))
    )
    (net (code "204") (name "unconnected-(J9-OW_DAT-Pad12)") (class "Default")
      (node (ref "J9") (pin "12") (pinfunction "OW_DAT_12") (pintype "bidirectional"))
    )
    (net (code "205") (name "unconnected-(J9-SDHC_DAT3-Pad15)") (class "Default")
      (node (ref "J9") (pin "15") (pinfunction "SDHC_DAT3_15") (pintype "bidirectional"))
    )
    (net (code "206") (name "unconnected-(J9-SPEEDLED-Pad40)") (class "Default")
      (node (ref "J9") (pin "40") (pinfunction "SPEEDLED_40") (pintype "bidirectional"))
    )
    (net (code "207") (name "unconnected-(J9-T0IN-Pad19)") (class "Default")
      (node (ref "J9") (pin "19") (pinfunction "T0IN_19") (pintype "bidirectional"))
    )
    (net (code "208") (name "unconnected-(J9-T1IN-Pad21)") (class "Default")
      (node (ref "J9") (pin "21") (pinfunction "T1IN_21") (pintype "bidirectional"))
    )
    (net (code "209") (name "unconnected-(J9-T3IN-Pad25)") (class "Default")
      (node (ref "J9") (pin "25") (pinfunction "T3IN_25") (pintype "bidirectional"))
    )
    (net (code "210") (name "unconnected-(J9-UART0_CTS-Pad30)") (class "Default")
      (node (ref "J9") (pin "30") (pinfunction "UART0_CTS_30") (pintype "bidirectional"))
    )
    (net (code "211") (name "unconnected-(J9-UART0_RTS-Pad28)") (class "Default")
      (node (ref "J9") (pin "28") (pinfunction "UART0_RTS_28") (pintype "bidirectional"))
    )
    (net (code "212") (name "unconnected-(J9-UART2_CTS-Pad10)") (class "Default")
      (node (ref "J9") (pin "10") (pinfunction "UART2_CTS_10") (pintype "bidirectional"))
    )
    (net (code "213") (name "unconnected-(J9-UART2_RTS-Pad14)") (class "Default")
      (node (ref "J9") (pin "14") (pinfunction "UART2_RTS_14") (pintype "bidirectional"))
    )
    (net (code "214") (name "unconnected-(J9-UART2_RX-Pad13)") (class "Default")
      (node (ref "J9") (pin "13") (pinfunction "UART2_RX_13") (pintype "bidirectional"))
    )
    (net (code "215") (name "unconnected-(J9-UART2_TX-Pad16)") (class "Default")
      (node (ref "J9") (pin "16") (pinfunction "UART2_TX_16") (pintype "bidirectional"))
    )
    (net (code "216") (name "unconnected-(J9-USBO_DM-Pad51)") (class "Default")
      (node (ref "J9") (pin "51") (pinfunction "USBO_DM_51") (pintype "bidirectional"))
    )
    (net (code "217") (name "unconnected-(J9-USBO_DP-Pad52)") (class "Default")
      (node (ref "J9") (pin "52") (pinfunction "USBO_DP_52") (pintype "bidirectional"))
    )
    (net (code "218") (name "unconnected-(J9-VCC3VE-Pad41)") (class "Default")
      (node (ref "J9") (pin "41") (pinfunction "VCC3VE_41") (pintype "bidirectional"))
    )
    (net (code "219") (name "unconnected-(J9-VDDA_DAC_ADC-Pad7)") (class "Default")
      (node (ref "J9") (pin "7") (pinfunction "VDDA_DAC_ADC_7") (pintype "bidirectional"))
    )
    (net (code "220") (name "unconnected-(OK1-A2-Pad3)") (class "Default")
      (node (ref "OK1") (pin "3") (pinfunction "A2_3") (pintype "bidirectional"))
    )
    (net (code "221") (name "unconnected-(OK1-A3-Pad5)") (class "Default")
      (node (ref "OK1") (pin "5") (pinfunction "A3_5") (pintype "bidirectional"))
    )
    (net (code "222") (name "unconnected-(OK1-A4-Pad7)") (class "Default")
      (node (ref "OK1") (pin "7") (pinfunction "A4_7") (pintype "bidirectional"))
    )
    (net (code "223") (name "unconnected-(OK1-C2-Pad14)") (class "Default")
      (node (ref "OK1") (pin "14") (pinfunction "C2_14") (pintype "bidirectional"))
    )
    (net (code "224") (name "unconnected-(OK1-C3-Pad12)") (class "Default")
      (node (ref "OK1") (pin "12") (pinfunction "C3_12") (pintype "bidirectional"))
    )
    (net (code "225") (name "unconnected-(OK1-C4-Pad10)") (class "Default")
      (node (ref "OK1") (pin "10") (pinfunction "C4_10") (pintype "bidirectional"))
    )
    (net (code "226") (name "unconnected-(OK1-E2-Pad13)") (class "Default")
      (node (ref "OK1") (pin "13") (pinfunction "E2_13") (pintype "bidirectional"))
    )
    (net (code "227") (name "unconnected-(OK1-E3-Pad11)") (class "Default")
      (node (ref "OK1") (pin "11") (pinfunction "E3_11") (pintype "bidirectional"))
    )
    (net (code "228") (name "unconnected-(OK1-E4-Pad9)") (class "Default")
      (node (ref "OK1") (pin "9") (pinfunction "E4_9") (pintype "bidirectional"))
    )
    (net (code "229") (name "unconnected-(OK1-K2-Pad4)") (class "Default")
      (node (ref "OK1") (pin "4") (pinfunction "K2_4") (pintype "bidirectional"))
    )
    (net (code "230") (name "unconnected-(OK1-K3-Pad6)") (class "Default")
      (node (ref "OK1") (pin "6") (pinfunction "K3_6") (pintype "bidirectional"))
    )
    (net (code "231") (name "unconnected-(OK1-K4-Pad8)") (class "Default")
      (node (ref "OK1") (pin "8") (pinfunction "K4_8") (pintype "bidirectional"))
    )
    (net (code "232") (name "unconnected-(U1-COMP-PadB7)") (class "Default")
      (node (ref "U1") (pin "B7") (pinfunction "COMP_B7") (pintype "bidirectional"))
    )
    (net (code "233") (name "unconnected-(U1-EXTV_CC-PadF6)") (class "Default")
      (node (ref "U1") (pin "F6") (pinfunction "EXTV_CC_F6") (pintype "bidirectional"))
    )
    (net (code "234") (name "unconnected-(U1-PLLIN-PadB9)") (class "Default")
      (node (ref "U1") (pin "B9") (pinfunction "PLLIN_B9") (pintype "bidirectional"))
    )
    (net (code "235") (name "unconnected-(U1-SS-PadA6)") (class "Default")
      (node (ref "U1") (pin "A6") (pinfunction "SS_A6") (pintype "bidirectional"))
    )
    (net (code "236") (name "unconnected-(U1-STBYMD-PadA10)") (class "Default")
      (node (ref "U1") (pin "A10") (pinfunction "STBYMD_A10") (pintype "bidirectional"))
    )
    (net (code "237") (name "unconnected-(U3-TIMER1-Pad2)") (class "Default")
      (node (ref "U3") (pin "2") (pinfunction "TIMER1_2") (pintype "bidirectional"))
    )
    (net (code "238") (name "unconnected-(U3-TIMER2-Pad4)") (class "Default")
      (node (ref "U3") (pin "4") (pinfunction "TIMER2_4") (pintype "bidirectional"))
    )
    (net (code "239") (name "unconnected-(U3-TIMER3-Pad6)") (class "Default")
      (node (ref "U3") (pin "6") (pinfunction "TIMER3_6") (pintype "bidirectional"))
    )
    (net (code "240") (name "unconnected-(U3-TIMER4-Pad8)") (class "Default")
      (node (ref "U3") (pin "8") (pinfunction "TIMER4_8") (pintype "bidirectional"))
    )
    (net (code "241") (name "unconnected-(U4-TIMER1-Pad2)") (class "Default")
      (node (ref "U4") (pin "2") (pinfunction "TIMER1_2") (pintype "bidirectional"))
    )
    (net (code "242") (name "unconnected-(U4-TIMER2-Pad4)") (class "Default")
      (node (ref "U4") (pin "4") (pinfunction "TIMER2_4") (pintype "bidirectional"))
    )
    (net (code "243") (name "unconnected-(U4-TIMER3-Pad6)") (class "Default")
      (node (ref "U4") (pin "6") (pinfunction "TIMER3_6") (pintype "bidirectional"))
    )
    (net (code "244") (name "unconnected-(U4-TIMER4-Pad8)") (class "Default")
      (node (ref "U4") (pin "8") (pinfunction "TIMER4_8") (pintype "bidirectional"))
    )
    (net (code "245") (name "~{RSTI}") (class "Default")
      (node (ref "J9") (pin "11") (pinfunction "RSTI_11") (pintype "bidirectional"))
      (node (ref "SW1") (pin "A") (pinfunction "P_A") (pintype "passive"))
      (node (ref "SW1") (pin "A'") (pinfunction "P1_A'") (pintype "passive"))
    )
  )
)
